# led_table_final.net
KiCad netlist of a schematic drawn in EAGLE
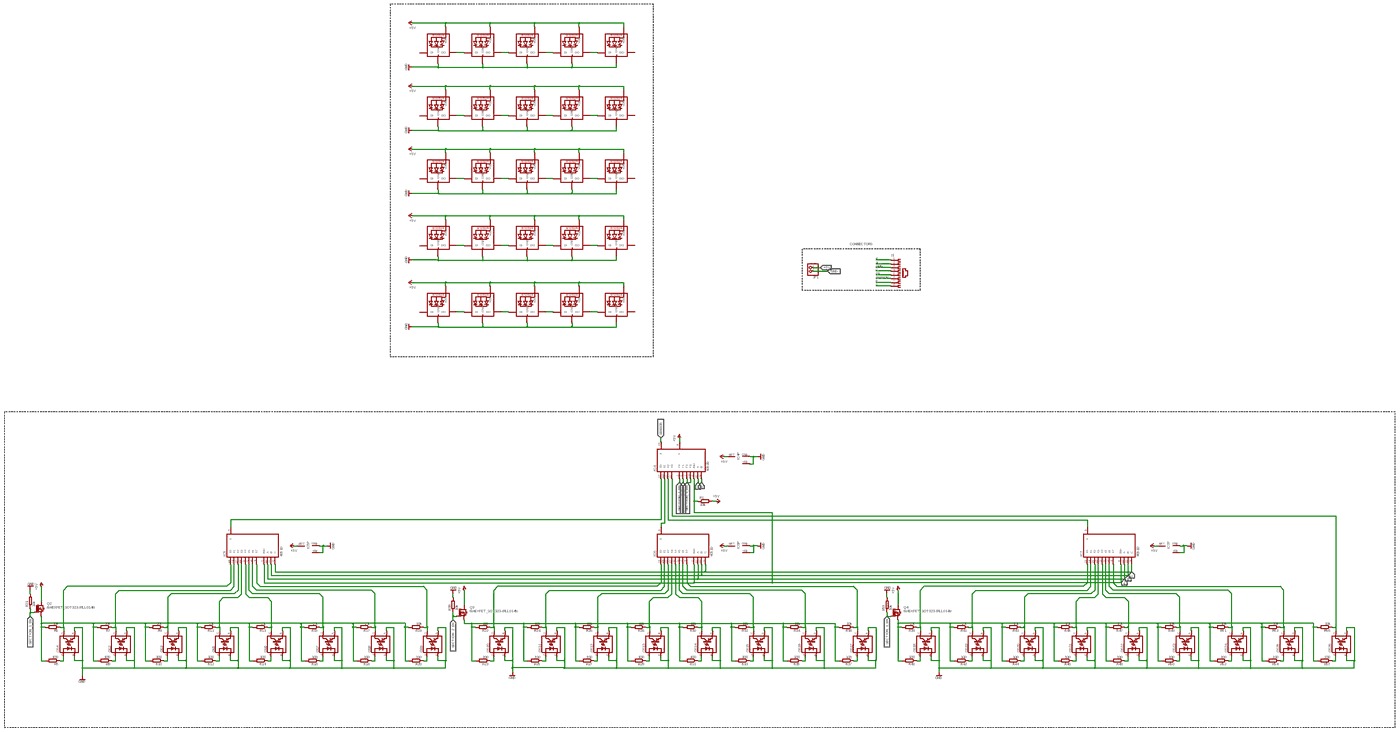
[diagram p0: schematic, sheet 1, overview]
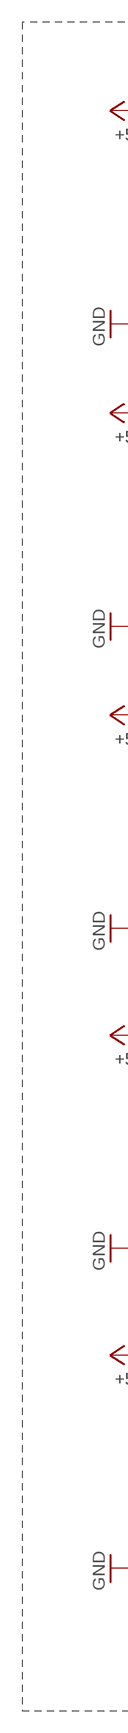
[diagram p1: schematic, sheet 1, part 1 of 5]
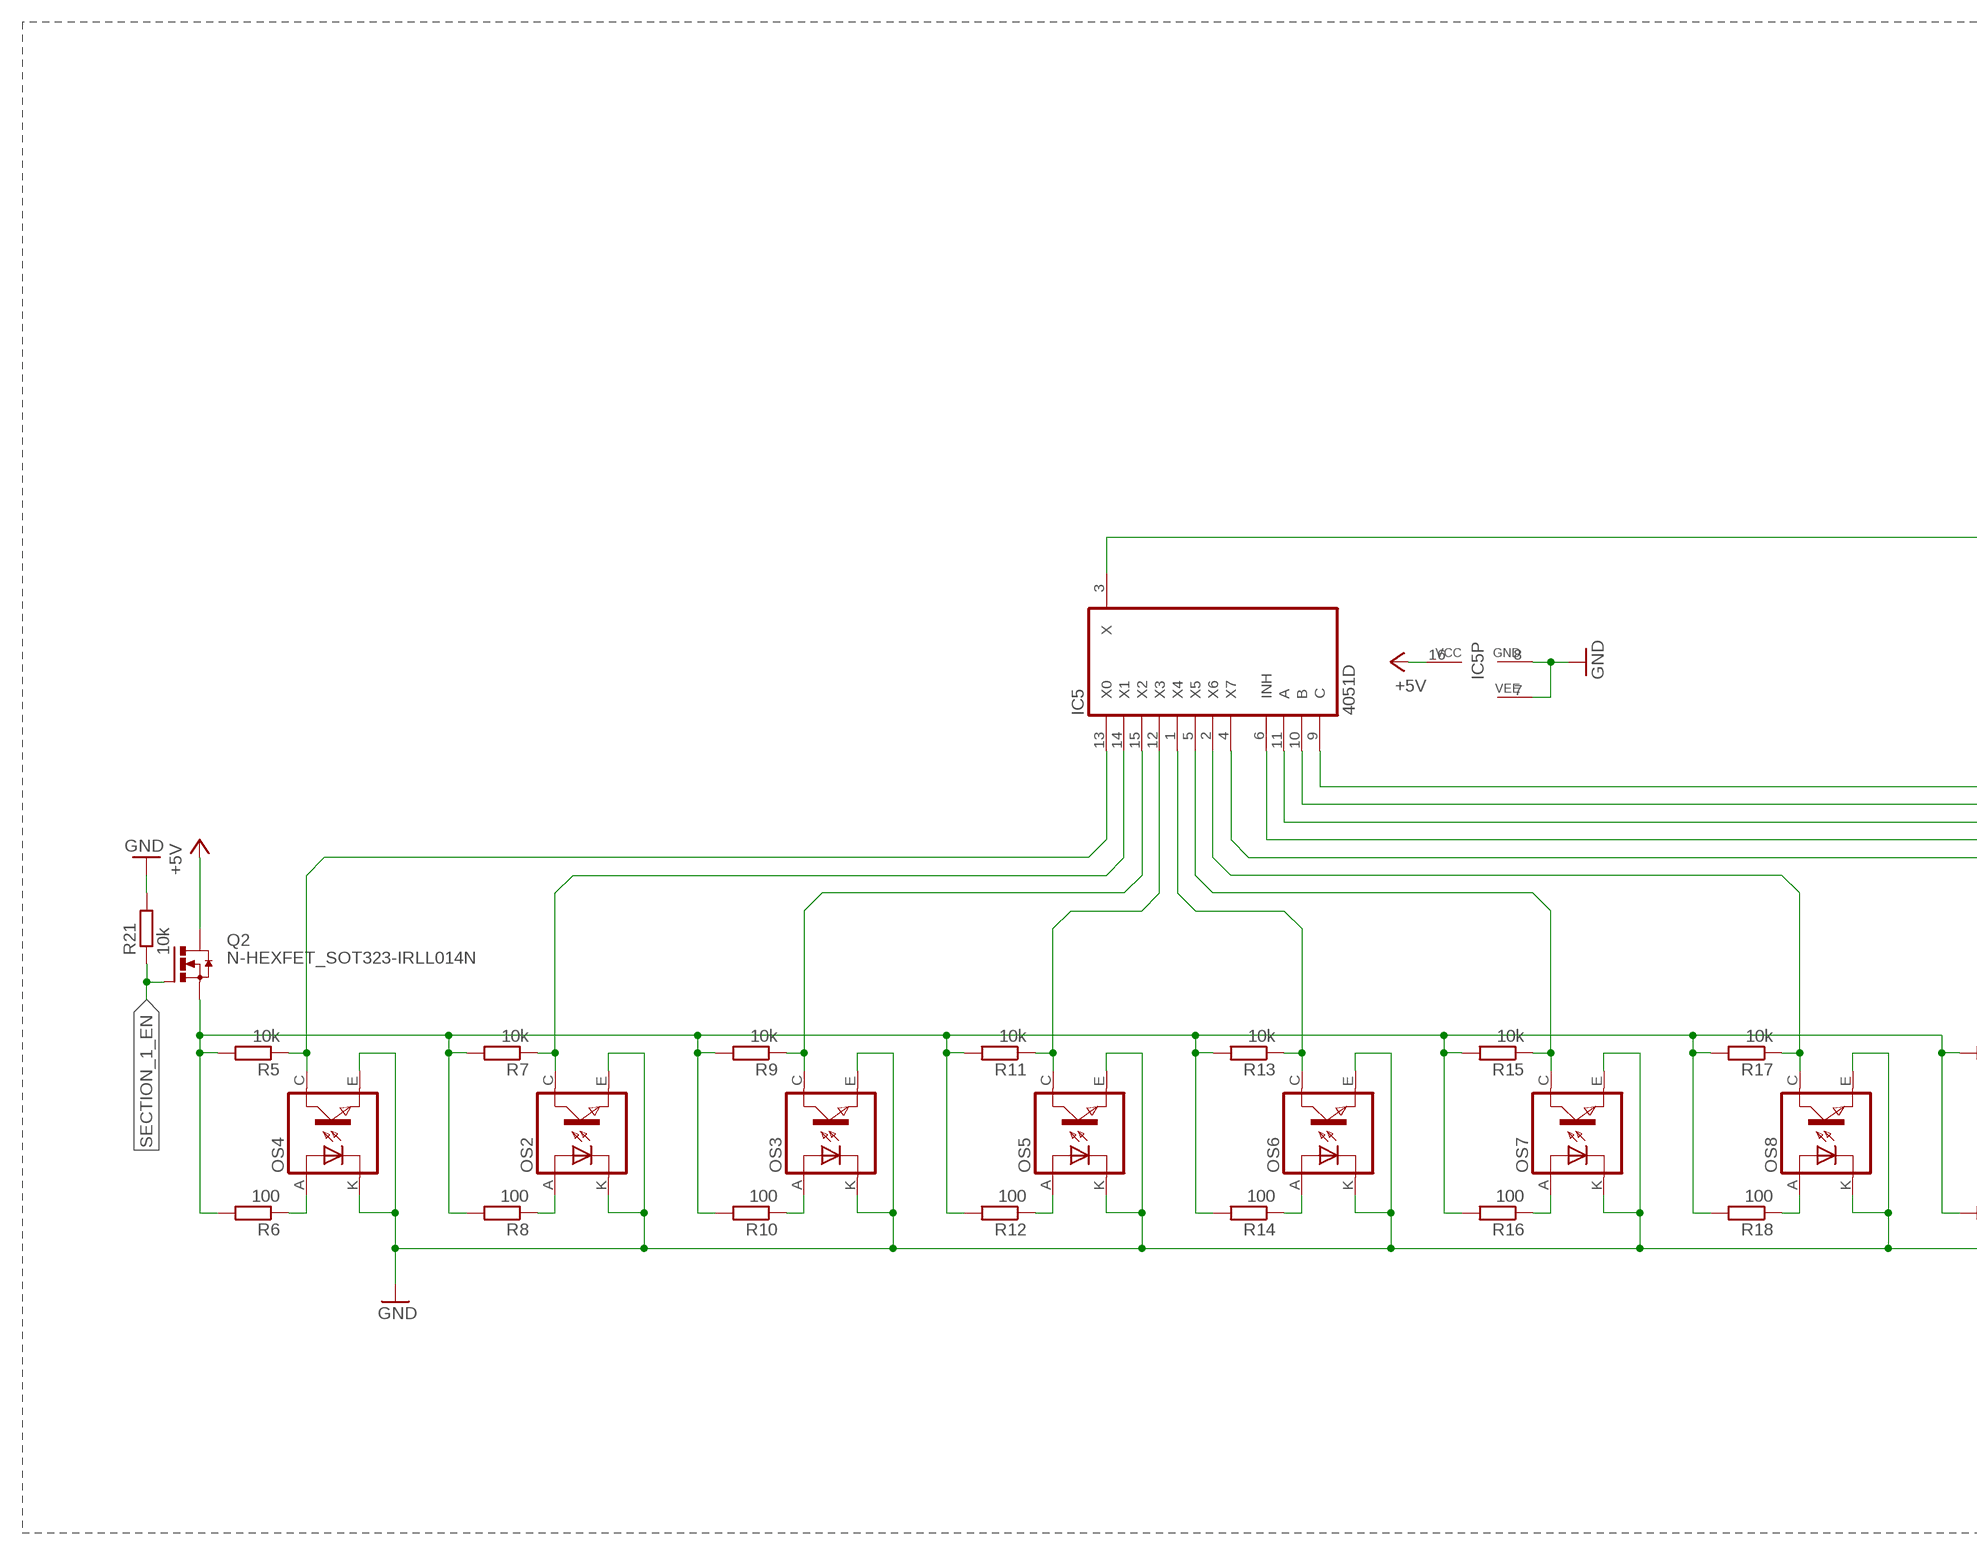
[diagram p2: schematic, sheet 1, part 2 of 5]
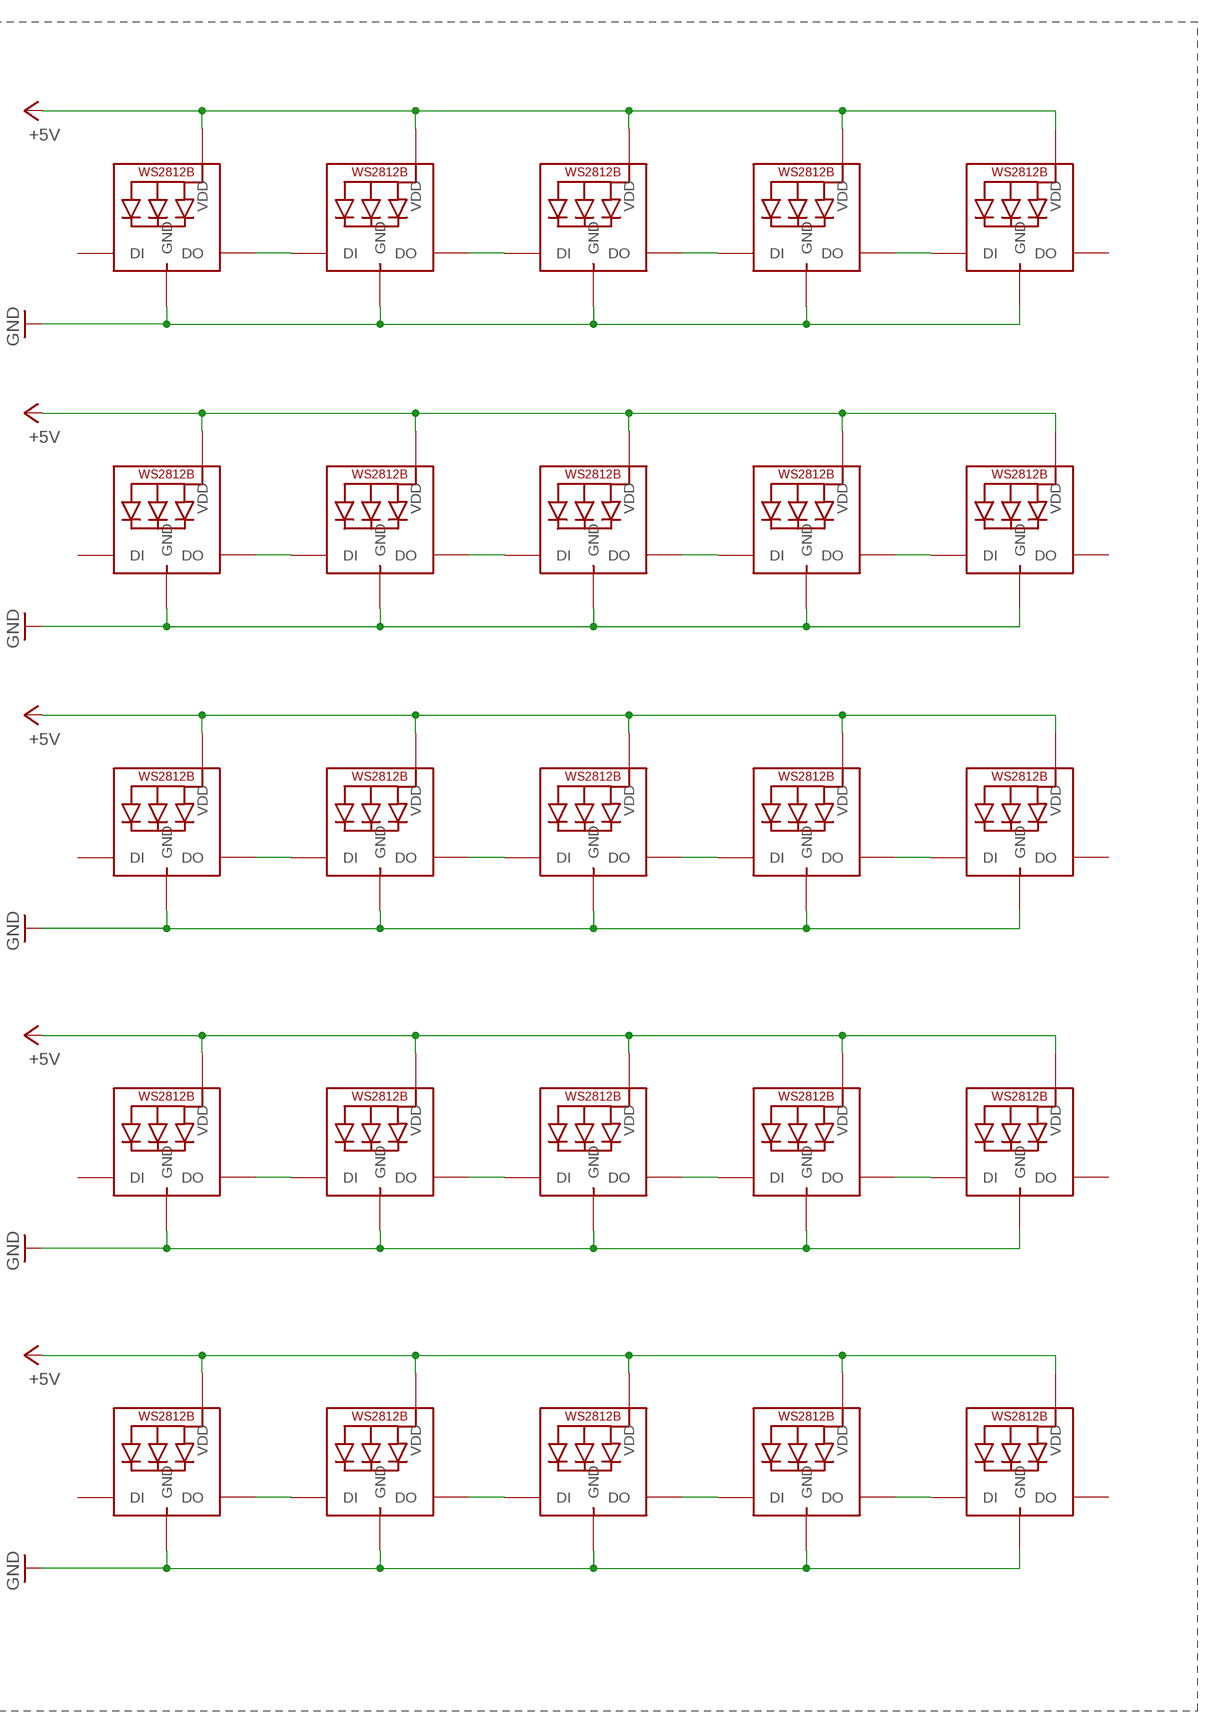
[diagram p3: schematic, sheet 1, part 3 of 5]
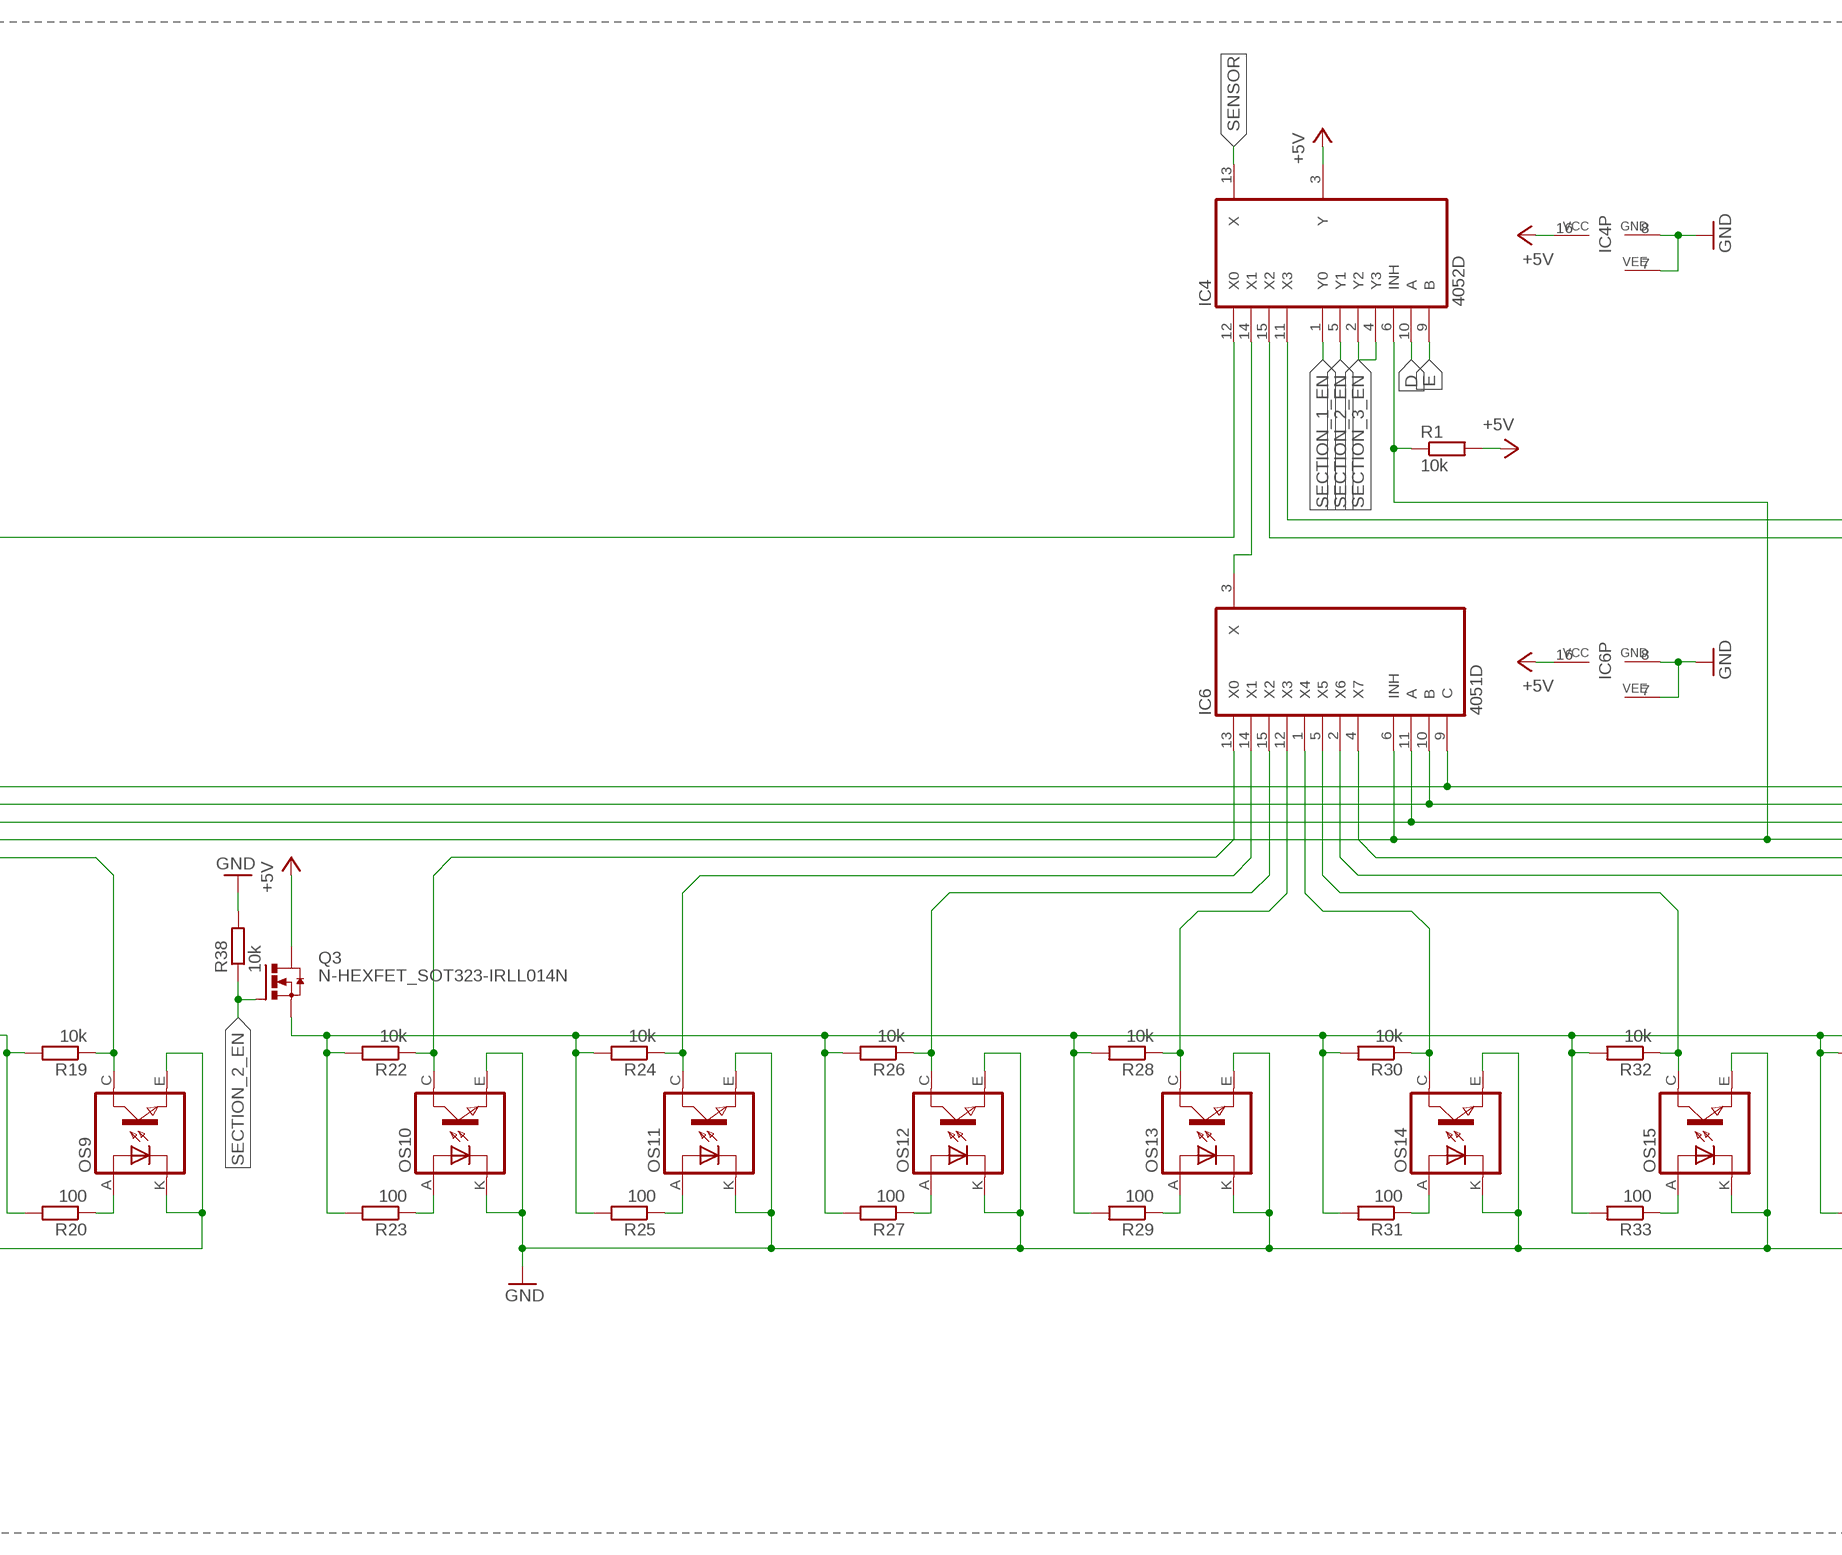
[diagram p4: schematic, sheet 1, part 4 of 5]
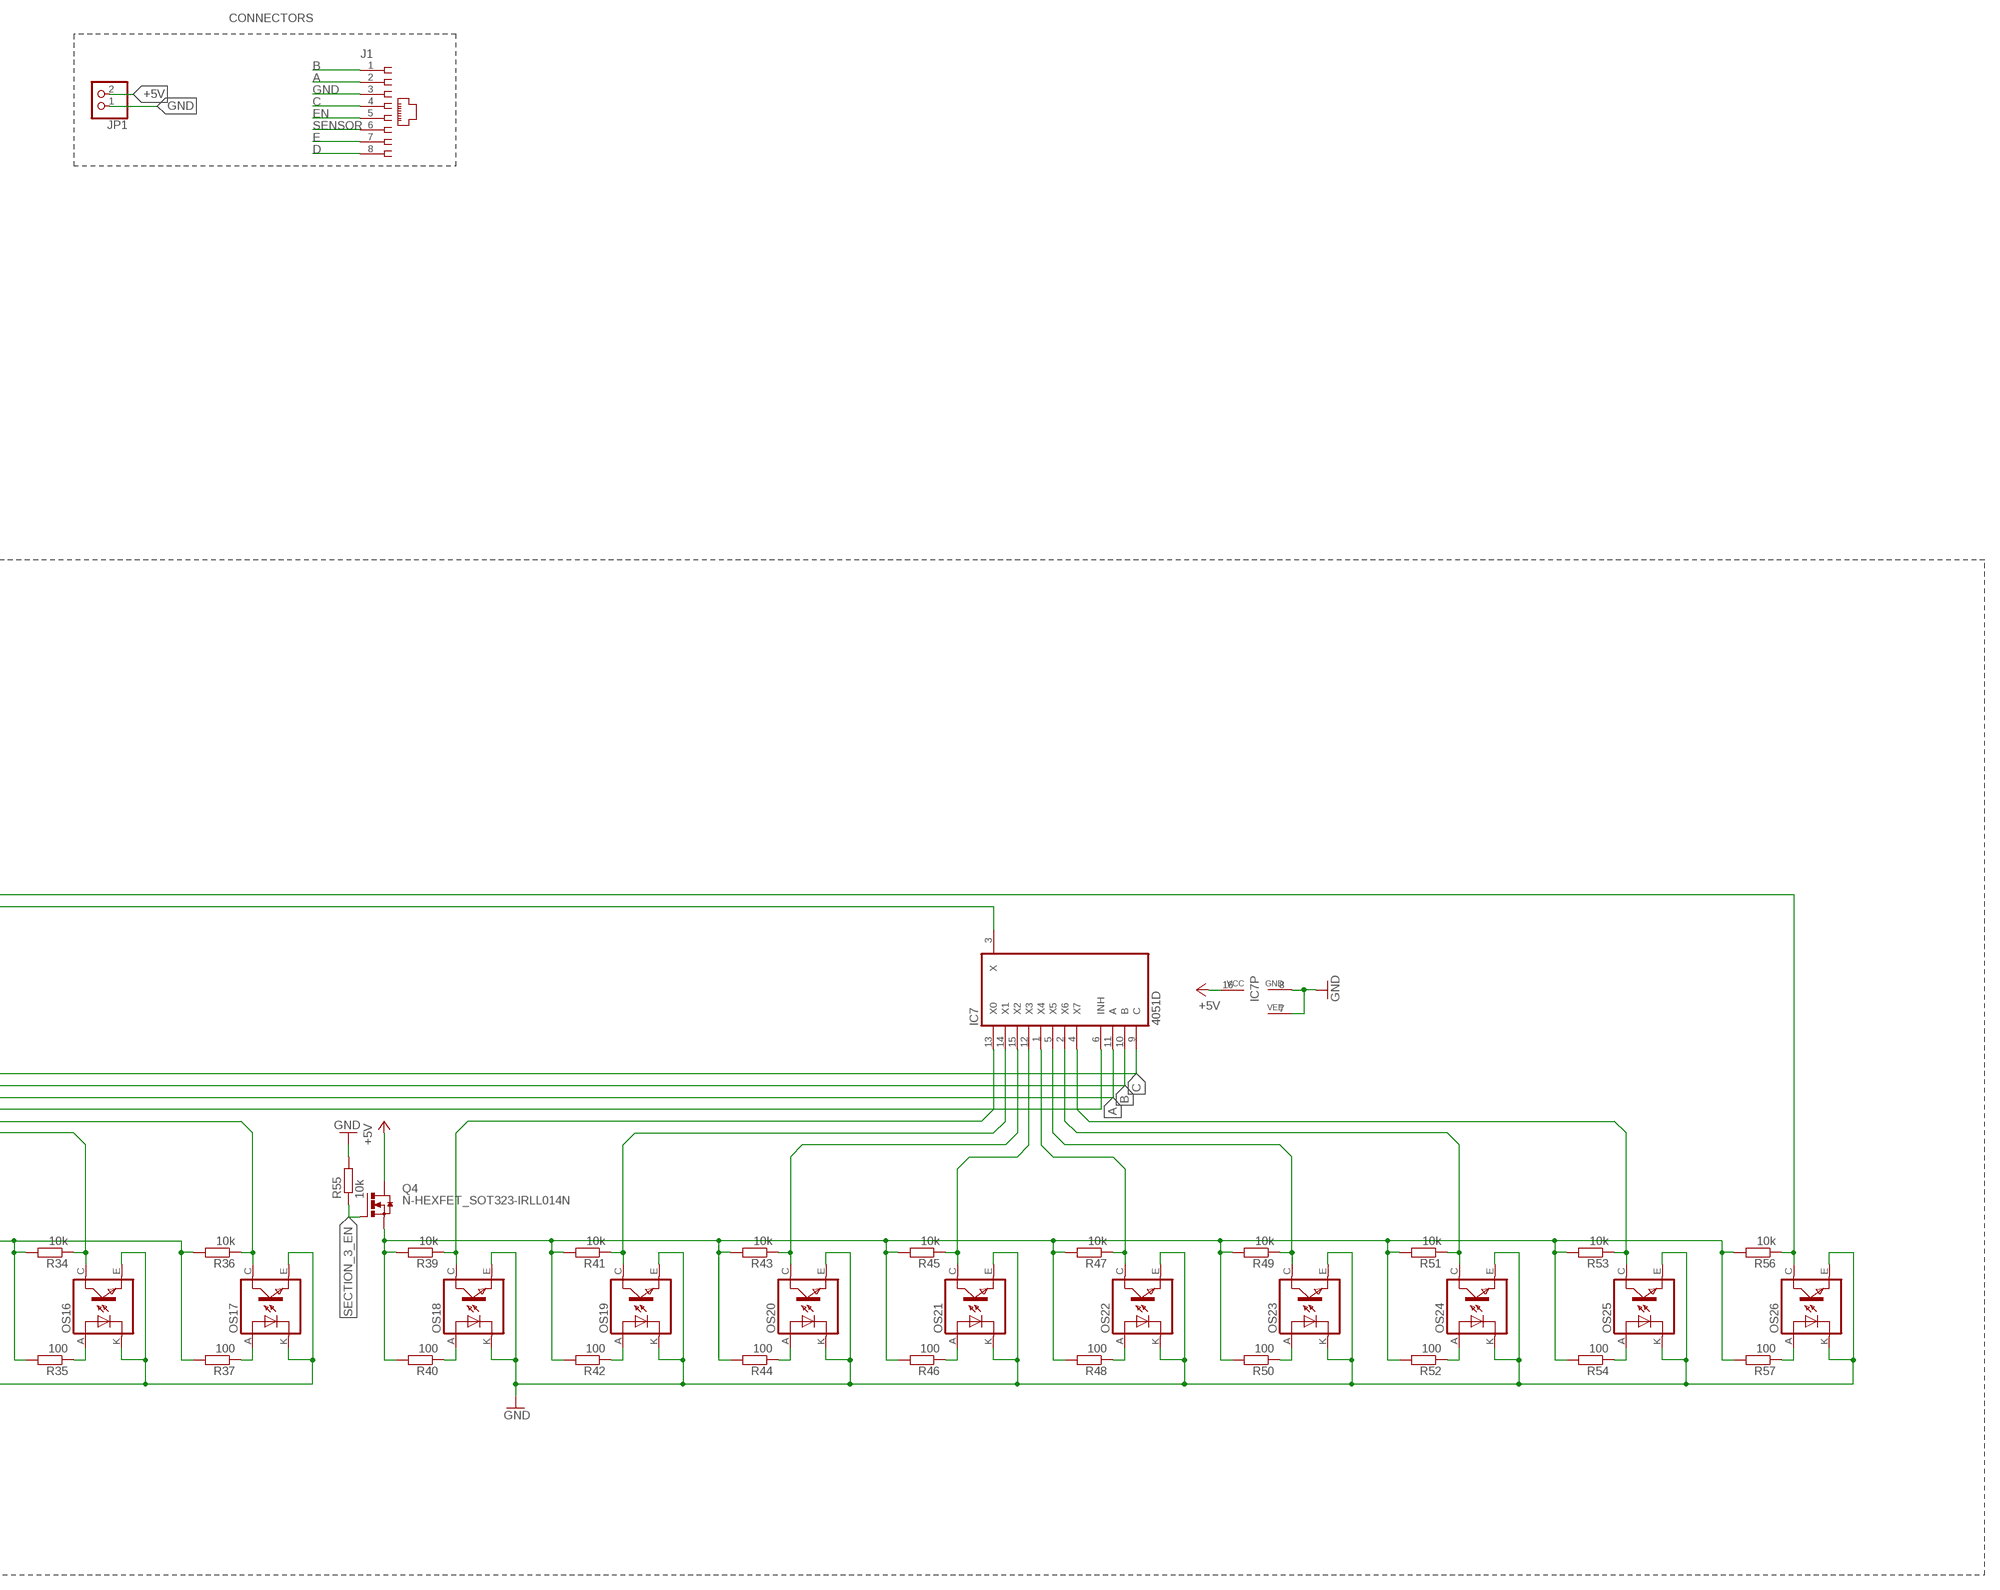
[diagram p5: schematic, sheet 1, part 5 of 5]

(export (version "E")
  (design (tool "Eeschema 10.0.6"))
  (components
    (comp (ref "IC4")
      (value "4052D")
      (footprint "eagle-import:SO16")
      (libsource (lib "eagle-import") (part "4052D"))
    )
    (comp (ref "IC5")
      (value "4051D")
      (footprint "eagle-import:SO16")
      (libsource (lib "eagle-import") (part "4051D"))
    )
    (comp (ref "IC6")
      (value "4051D")
      (footprint "eagle-import:SO16")
      (libsource (lib "eagle-import") (part "4051D"))
    )
    (comp (ref "IC7")
      (value "4051D")
      (footprint "eagle-import:SO16")
      (libsource (lib "eagle-import") (part "4051D"))
    )
    (comp (ref "J1")
      (value "556416-1")
      (footprint "eagle-import:556416-1")
      (libsource (lib "eagle-import") (part "556416-1"))
    )
    (comp (ref "JP1")
      (value "PINHD-1X2")
      (footprint "eagle-import:1X02")
      (libsource (lib "eagle-import") (part "PINHD-1X2"))
    )
    (comp (ref "LED1")
      (value "WS2812B")
      (footprint "eagle-import:WS2812B_ON_STRIP")
      (libsource (lib "eagle-import") (part "WS2812B"))
    )
    (comp (ref "LED2")
      (value "WS2812B")
      (footprint "eagle-import:WS2812B_ON_STRIP")
      (libsource (lib "eagle-import") (part "WS2812B"))
    )
    (comp (ref "LED3")
      (value "WS2812B")
      (footprint "eagle-import:WS2812B_ON_STRIP")
      (libsource (lib "eagle-import") (part "WS2812B"))
    )
    (comp (ref "LED4")
      (value "WS2812B")
      (footprint "eagle-import:WS2812B_ON_STRIP")
      (libsource (lib "eagle-import") (part "WS2812B"))
    )
    (comp (ref "LED5")
      (value "WS2812B")
      (footprint "eagle-import:WS2812B_ON_STRIP")
      (libsource (lib "eagle-import") (part "WS2812B"))
    )
    (comp (ref "LED6")
      (value "WS2812B")
      (footprint "eagle-import:WS2812B_ON_STRIP")
      (libsource (lib "eagle-import") (part "WS2812B"))
    )
    (comp (ref "LED7")
      (value "WS2812B")
      (footprint "eagle-import:WS2812B_ON_STRIP")
      (libsource (lib "eagle-import") (part "WS2812B"))
    )
    (comp (ref "LED8")
      (value "WS2812B")
      (footprint "eagle-import:WS2812B_ON_STRIP")
      (libsource (lib "eagle-import") (part "WS2812B"))
    )
    (comp (ref "LED9")
      (value "WS2812B")
      (footprint "eagle-import:WS2812B_ON_STRIP")
      (libsource (lib "eagle-import") (part "WS2812B"))
    )
    (comp (ref "LED10")
      (value "WS2812B")
      (footprint "eagle-import:WS2812B_ON_STRIP")
      (libsource (lib "eagle-import") (part "WS2812B"))
    )
    (comp (ref "LED11")
      (value "WS2812B")
      (footprint "eagle-import:WS2812B_ON_STRIP")
      (libsource (lib "eagle-import") (part "WS2812B"))
    )
    (comp (ref "LED12")
      (value "WS2812B")
      (footprint "eagle-import:WS2812B_ON_STRIP")
      (libsource (lib "eagle-import") (part "WS2812B"))
    )
    (comp (ref "LED13")
      (value "WS2812B")
      (footprint "eagle-import:WS2812B_ON_STRIP")
      (libsource (lib "eagle-import") (part "WS2812B"))
    )
    (comp (ref "LED14")
      (value "WS2812B")
      (footprint "eagle-import:WS2812B_ON_STRIP")
      (libsource (lib "eagle-import") (part "WS2812B"))
    )
    (comp (ref "LED15")
      (value "WS2812B")
      (footprint "eagle-import:WS2812B_ON_STRIP")
      (libsource (lib "eagle-import") (part "WS2812B"))
    )
    (comp (ref "LED16")
      (value "WS2812B")
      (footprint "eagle-import:WS2812B_ON_STRIP")
      (libsource (lib "eagle-import") (part "WS2812B"))
    )
    (comp (ref "LED17")
      (value "WS2812B")
      (footprint "eagle-import:WS2812B_ON_STRIP")
      (libsource (lib "eagle-import") (part "WS2812B"))
    )
    (comp (ref "LED18")
      (value "WS2812B")
      (footprint "eagle-import:WS2812B_ON_STRIP")
      (libsource (lib "eagle-import") (part "WS2812B"))
    )
    (comp (ref "LED19")
      (value "WS2812B")
      (footprint "eagle-import:WS2812B_ON_STRIP")
      (libsource (lib "eagle-import") (part "WS2812B"))
    )
    (comp (ref "LED20")
      (value "WS2812B")
      (footprint "eagle-import:WS2812B_ON_STRIP")
      (libsource (lib "eagle-import") (part "WS2812B"))
    )
    (comp (ref "LED21")
      (value "WS2812B")
      (footprint "eagle-import:WS2812B_ON_STRIP")
      (libsource (lib "eagle-import") (part "WS2812B"))
    )
    (comp (ref "LED22")
      (value "WS2812B")
      (footprint "eagle-import:WS2812B_ON_STRIP")
      (libsource (lib "eagle-import") (part "WS2812B"))
    )
    (comp (ref "LED23")
      (value "WS2812B")
      (footprint "eagle-import:WS2812B_ON_STRIP")
      (libsource (lib "eagle-import") (part "WS2812B"))
    )
    (comp (ref "LED24")
      (value "WS2812B")
      (footprint "eagle-import:WS2812B_ON_STRIP")
      (libsource (lib "eagle-import") (part "WS2812B"))
    )
    (comp (ref "LED25")
      (value "WS2812B")
      (footprint "eagle-import:WS2812B_ON_STRIP")
      (libsource (lib "eagle-import") (part "WS2812B"))
    )
    (comp (ref "OS2")
      (value "TCRT5000")
      (footprint "eagle-import:TCRT5000")
      (libsource (lib "eagle-import") (part "TCRT5000"))
    )
    (comp (ref "OS3")
      (value "TCRT5000")
      (footprint "eagle-import:TCRT5000")
      (libsource (lib "eagle-import") (part "TCRT5000"))
    )
    (comp (ref "OS4")
      (value "TCRT5000")
      (footprint "eagle-import:TCRT5000")
      (libsource (lib "eagle-import") (part "TCRT5000"))
    )
    (comp (ref "OS5")
      (value "TCRT5000")
      (footprint "eagle-import:TCRT5000")
      (libsource (lib "eagle-import") (part "TCRT5000"))
    )
    (comp (ref "OS6")
      (value "TCRT5000")
      (footprint "eagle-import:TCRT5000")
      (libsource (lib "eagle-import") (part "TCRT5000"))
    )
    (comp (ref "OS7")
      (value "TCRT5000")
      (footprint "eagle-import:TCRT5000")
      (libsource (lib "eagle-import") (part "TCRT5000"))
    )
    (comp (ref "OS8")
      (value "TCRT5000")
      (footprint "eagle-import:TCRT5000")
      (libsource (lib "eagle-import") (part "TCRT5000"))
    )
    (comp (ref "OS9")
      (value "TCRT5000")
      (footprint "eagle-import:TCRT5000")
      (libsource (lib "eagle-import") (part "TCRT5000"))
    )
    (comp (ref "OS10")
      (value "TCRT5000")
      (footprint "eagle-import:TCRT5000")
      (libsource (lib "eagle-import") (part "TCRT5000"))
    )
    (comp (ref "OS11")
      (value "TCRT5000")
      (footprint "eagle-import:TCRT5000")
      (libsource (lib "eagle-import") (part "TCRT5000"))
    )
    (comp (ref "OS12")
      (value "TCRT5000")
      (footprint "eagle-import:TCRT5000")
      (libsource (lib "eagle-import") (part "TCRT5000"))
    )
    (comp (ref "OS13")
      (value "TCRT5000")
      (footprint "eagle-import:TCRT5000")
      (libsource (lib "eagle-import") (part "TCRT5000"))
    )
    (comp (ref "OS14")
      (value "TCRT5000")
      (footprint "eagle-import:TCRT5000")
      (libsource (lib "eagle-import") (part "TCRT5000"))
    )
    (comp (ref "OS15")
      (value "TCRT5000")
      (footprint "eagle-import:TCRT5000")
      (libsource (lib "eagle-import") (part "TCRT5000"))
    )
    (comp (ref "OS16")
      (value "TCRT5000")
      (footprint "eagle-import:TCRT5000")
      (libsource (lib "eagle-import") (part "TCRT5000"))
    )
    (comp (ref "OS17")
      (value "TCRT5000")
      (footprint "eagle-import:TCRT5000")
      (libsource (lib "eagle-import") (part "TCRT5000"))
    )
    (comp (ref "OS18")
      (value "TCRT5000")
      (footprint "eagle-import:TCRT5000")
      (libsource (lib "eagle-import") (part "TCRT5000"))
    )
    (comp (ref "OS19")
      (value "TCRT5000")
      (footprint "eagle-import:TCRT5000")
      (libsource (lib "eagle-import") (part "TCRT5000"))
    )
    (comp (ref "OS20")
      (value "TCRT5000")
      (footprint "eagle-import:TCRT5000")
      (libsource (lib "eagle-import") (part "TCRT5000"))
    )
    (comp (ref "OS21")
      (value "TCRT5000")
      (footprint "eagle-import:TCRT5000")
      (libsource (lib "eagle-import") (part "TCRT5000"))
    )
    (comp (ref "OS22")
      (value "TCRT5000")
      (footprint "eagle-import:TCRT5000")
      (libsource (lib "eagle-import") (part "TCRT5000"))
    )
    (comp (ref "OS23")
      (value "TCRT5000")
      (footprint "eagle-import:TCRT5000")
      (libsource (lib "eagle-import") (part "TCRT5000"))
    )
    (comp (ref "OS24")
      (value "TCRT5000")
      (footprint "eagle-import:TCRT5000")
      (libsource (lib "eagle-import") (part "TCRT5000"))
    )
    (comp (ref "OS25")
      (value "TCRT5000")
      (footprint "eagle-import:TCRT5000")
      (libsource (lib "eagle-import") (part "TCRT5000"))
    )
    (comp (ref "OS26")
      (value "TCRT5000")
      (footprint "eagle-import:TCRT5000")
      (libsource (lib "eagle-import") (part "TCRT5000"))
    )
    (comp (ref "Q2")
      (value "N-HEXFET_SOT323-IRLL014N")
      (footprint "eagle-import:SOT223")
      (libsource (lib "eagle-import") (part "N-HEXFET_?-SOT323IRLL014N"))
    )
    (comp (ref "Q3")
      (value "N-HEXFET_SOT323-IRLL014N")
      (footprint "eagle-import:SOT223")
      (libsource (lib "eagle-import") (part "N-HEXFET_?-SOT323IRLL014N"))
    )
    (comp (ref "Q4")
      (value "N-HEXFET_SOT323-IRLL014N")
      (footprint "eagle-import:SOT223")
      (libsource (lib "eagle-import") (part "N-HEXFET_?-SOT323IRLL014N"))
    )
    (comp (ref "R1")
      (value "10k")
      (footprint "eagle-import:R1206")
      (libsource (lib "eagle-import") (part "R-EU_R1206"))
    )
    (comp (ref "R5")
      (value "10k")
      (footprint "eagle-import:R1206")
      (libsource (lib "eagle-import") (part "R-EU_R1206"))
    )
    (comp (ref "R6")
      (value "100")
      (footprint "eagle-import:R1206")
      (libsource (lib "eagle-import") (part "R-EU_R1206"))
    )
    (comp (ref "R7")
      (value "10k")
      (footprint "eagle-import:R1206")
      (libsource (lib "eagle-import") (part "R-EU_R1206"))
    )
    (comp (ref "R8")
      (value "100")
      (footprint "eagle-import:R1206")
      (libsource (lib "eagle-import") (part "R-EU_R1206"))
    )
    (comp (ref "R9")
      (value "10k")
      (footprint "eagle-import:R1206")
      (libsource (lib "eagle-import") (part "R-EU_R1206"))
    )
    (comp (ref "R10")
      (value "100")
      (footprint "eagle-import:R1206")
      (libsource (lib "eagle-import") (part "R-EU_R1206"))
    )
    (comp (ref "R11")
      (value "10k")
      (footprint "eagle-import:R1206")
      (libsource (lib "eagle-import") (part "R-EU_R1206"))
    )
    (comp (ref "R12")
      (value "100")
      (footprint "eagle-import:R1206")
      (libsource (lib "eagle-import") (part "R-EU_R1206"))
    )
    (comp (ref "R13")
      (value "10k")
      (footprint "eagle-import:R1206")
      (libsource (lib "eagle-import") (part "R-EU_R1206"))
    )
    (comp (ref "R14")
      (value "100")
      (footprint "eagle-import:R1206")
      (libsource (lib "eagle-import") (part "R-EU_R1206"))
    )
    (comp (ref "R15")
      (value "10k")
      (footprint "eagle-import:R1206")
      (libsource (lib "eagle-import") (part "R-EU_R1206"))
    )
    (comp (ref "R16")
      (value "100")
      (footprint "eagle-import:R1206")
      (libsource (lib "eagle-import") (part "R-EU_R1206"))
    )
    (comp (ref "R17")
      (value "10k")
      (footprint "eagle-import:R1206")
      (libsource (lib "eagle-import") (part "R-EU_R1206"))
    )
    (comp (ref "R18")
      (value "100")
      (footprint "eagle-import:R1206")
      (libsource (lib "eagle-import") (part "R-EU_R1206"))
    )
    (comp (ref "R19")
      (value "10k")
      (footprint "eagle-import:R1206")
      (libsource (lib "eagle-import") (part "R-EU_R1206"))
    )
    (comp (ref "R20")
      (value "100")
      (footprint "eagle-import:R1206")
      (libsource (lib "eagle-import") (part "R-EU_R1206"))
    )
    (comp (ref "R21")
      (value "10k")
      (footprint "eagle-import:R1206")
      (libsource (lib "eagle-import") (part "R-EU_R1206"))
    )
    (comp (ref "R22")
      (value "10k")
      (footprint "eagle-import:R1206")
      (libsource (lib "eagle-import") (part "R-EU_R1206"))
    )
    (comp (ref "R23")
      (value "100")
      (footprint "eagle-import:R1206")
      (libsource (lib "eagle-import") (part "R-EU_R1206"))
    )
    (comp (ref "R24")
      (value "10k")
      (footprint "eagle-import:R1206")
      (libsource (lib "eagle-import") (part "R-EU_R1206"))
    )
    (comp (ref "R25")
      (value "100")
      (footprint "eagle-import:R1206")
      (libsource (lib "eagle-import") (part "R-EU_R1206"))
    )
    (comp (ref "R26")
      (value "10k")
      (footprint "eagle-import:R1206")
      (libsource (lib "eagle-import") (part "R-EU_R1206"))
    )
    (comp (ref "R27")
      (value "100")
      (footprint "eagle-import:R1206")
      (libsource (lib "eagle-import") (part "R-EU_R1206"))
    )
    (comp (ref "R28")
      (value "10k")
      (footprint "eagle-import:R1206")
      (libsource (lib "eagle-import") (part "R-EU_R1206"))
    )
    (comp (ref "R29")
      (value "100")
      (footprint "eagle-import:R1206")
      (libsource (lib "eagle-import") (part "R-EU_R1206"))
    )
    (comp (ref "R30")
      (value "10k")
      (footprint "eagle-import:R1206")
      (libsource (lib "eagle-import") (part "R-EU_R1206"))
    )
    (comp (ref "R31")
      (value "100")
      (footprint "eagle-import:R1206")
      (libsource (lib "eagle-import") (part "R-EU_R1206"))
    )
    (comp (ref "R32")
      (value "10k")
      (footprint "eagle-import:R1206")
      (libsource (lib "eagle-import") (part "R-EU_R1206"))
    )
    (comp (ref "R33")
      (value "100")
      (footprint "eagle-import:R1206")
      (libsource (lib "eagle-import") (part "R-EU_R1206"))
    )
    (comp (ref "R34")
      (value "10k")
      (footprint "eagle-import:R1206")
      (libsource (lib "eagle-import") (part "R-EU_R1206"))
    )
    (comp (ref "R35")
      (value "100")
      (footprint "eagle-import:R1206")
      (libsource (lib "eagle-import") (part "R-EU_R1206"))
    )
    (comp (ref "R36")
      (value "10k")
      (footprint "eagle-import:R1206")
      (libsource (lib "eagle-import") (part "R-EU_R1206"))
    )
    (comp (ref "R37")
      (value "100")
      (footprint "eagle-import:R1206")
      (libsource (lib "eagle-import") (part "R-EU_R1206"))
    )
    (comp (ref "R38")
      (value "10k")
      (footprint "eagle-import:R1206")
      (libsource (lib "eagle-import") (part "R-EU_R1206"))
    )
    (comp (ref "R39")
      (value "10k")
      (footprint "eagle-import:R1206")
      (libsource (lib "eagle-import") (part "R-EU_R1206"))
    )
    (comp (ref "R40")
      (value "100")
      (footprint "eagle-import:R1206")
      (libsource (lib "eagle-import") (part "R-EU_R1206"))
    )
    (comp (ref "R41")
      (value "10k")
      (footprint "eagle-import:R1206")
      (libsource (lib "eagle-import") (part "R-EU_R1206"))
    )
    (comp (ref "R42")
      (value "100")
      (footprint "eagle-import:R1206")
      (libsource (lib "eagle-import") (part "R-EU_R1206"))
    )
    (comp (ref "R43")
      (value "10k")
      (footprint "eagle-import:R1206")
      (libsource (lib "eagle-import") (part "R-EU_R1206"))
    )
    (comp (ref "R44")
      (value "100")
      (footprint "eagle-import:R1206")
      (libsource (lib "eagle-import") (part "R-EU_R1206"))
    )
    (comp (ref "R45")
      (value "10k")
      (footprint "eagle-import:R1206")
      (libsource (lib "eagle-import") (part "R-EU_R1206"))
    )
    (comp (ref "R46")
      (value "100")
      (footprint "eagle-import:R1206")
      (libsource (lib "eagle-import") (part "R-EU_R1206"))
    )
    (comp (ref "R47")
      (value "10k")
      (footprint "eagle-import:R1206")
      (libsource (lib "eagle-import") (part "R-EU_R1206"))
    )
    (comp (ref "R48")
      (value "100")
      (footprint "eagle-import:R1206")
      (libsource (lib "eagle-import") (part "R-EU_R1206"))
    )
    (comp (ref "R49")
      (value "10k")
      (footprint "eagle-import:R1206")
      (libsource (lib "eagle-import") (part "R-EU_R1206"))
    )
    (comp (ref "R50")
      (value "100")
      (footprint "eagle-import:R1206")
      (libsource (lib "eagle-import") (part "R-EU_R1206"))
    )
    (comp (ref "R51")
      (value "10k")
      (footprint "eagle-import:R1206")
      (libsource (lib "eagle-import") (part "R-EU_R1206"))
    )
    (comp (ref "R52")
      (value "100")
      (footprint "eagle-import:R1206")
      (libsource (lib "eagle-import") (part "R-EU_R1206"))
    )
    (comp (ref "R53")
      (value "10k")
      (footprint "eagle-import:R1206")
      (libsource (lib "eagle-import") (part "R-EU_R1206"))
    )
    (comp (ref "R54")
      (value "100")
      (footprint "eagle-import:R1206")
      (libsource (lib "eagle-import") (part "R-EU_R1206"))
    )
    (comp (ref "R55")
      (value "10k")
      (footprint "eagle-import:R1206")
      (libsource (lib "eagle-import") (part "R-EU_R1206"))
    )
    (comp (ref "R56")
      (value "10k")
      (footprint "eagle-import:R1206")
      (libsource (lib "eagle-import") (part "R-EU_R1206"))
    )
    (comp (ref "R57")
      (value "100")
      (footprint "eagle-import:R1206")
      (libsource (lib "eagle-import") (part "R-EU_R1206"))
    )
  )
  (nets
    (net (code "1") (name "+5V") (class "Default")
      (node (ref "IC4") (pin "16") (pinfunction "VCC_16") (pintype "power_in"))
      (node (ref "IC4") (pin "3") (pinfunction "Y_3") (pintype "bidirectional"))
      (node (ref "IC5") (pin "16") (pinfunction "VCC_16") (pintype "power_in"))
      (node (ref "IC6") (pin "16") (pinfunction "VCC_16") (pintype "power_in"))
      (node (ref "IC7") (pin "16") (pinfunction "VCC_16") (pintype "power_in"))
      (node (ref "JP1") (pin "2") (pinfunction "2_2") (pintype "passive"))
      (node (ref "LED1") (pin "VCC_IN") (pinfunction "VDD_VCC_IN") (pintype "power_in"))
      (node (ref "LED1") (pin "VCC_OUT") (pinfunction "VDD_VCC_OUT") (pintype "power_in"))
      (node (ref "LED10") (pin "VCC_IN") (pinfunction "VDD_VCC_IN") (pintype "power_in"))
      (node (ref "LED10") (pin "VCC_OUT") (pinfunction "VDD_VCC_OUT") (pintype "power_in"))
      (node (ref "LED11") (pin "VCC_IN") (pinfunction "VDD_VCC_IN") (pintype "power_in"))
      (node (ref "LED11") (pin "VCC_OUT") (pinfunction "VDD_VCC_OUT") (pintype "power_in"))
      (node (ref "LED12") (pin "VCC_IN") (pinfunction "VDD_VCC_IN") (pintype "power_in"))
      (node (ref "LED12") (pin "VCC_OUT") (pinfunction "VDD_VCC_OUT") (pintype "power_in"))
      (node (ref "LED13") (pin "VCC_IN") (pinfunction "VDD_VCC_IN") (pintype "power_in"))
      (node (ref "LED13") (pin "VCC_OUT") (pinfunction "VDD_VCC_OUT") (pintype "power_in"))
      (node (ref "LED14") (pin "VCC_IN") (pinfunction "VDD_VCC_IN") (pintype "power_in"))
      (node (ref "LED14") (pin "VCC_OUT") (pinfunction "VDD_VCC_OUT") (pintype "power_in"))
      (node (ref "LED15") (pin "VCC_IN") (pinfunction "VDD_VCC_IN") (pintype "power_in"))
      (node (ref "LED15") (pin "VCC_OUT") (pinfunction "VDD_VCC_OUT") (pintype "power_in"))
      (node (ref "LED16") (pin "VCC_IN") (pinfunction "VDD_VCC_IN") (pintype "power_in"))
      (node (ref "LED16") (pin "VCC_OUT") (pinfunction "VDD_VCC_OUT") (pintype "power_in"))
      (node (ref "LED17") (pin "VCC_IN") (pinfunction "VDD_VCC_IN") (pintype "power_in"))
      (node (ref "LED17") (pin "VCC_OUT") (pinfunction "VDD_VCC_OUT") (pintype "power_in"))
      (node (ref "LED18") (pin "VCC_IN") (pinfunction "VDD_VCC_IN") (pintype "power_in"))
      (node (ref "LED18") (pin "VCC_OUT") (pinfunction "VDD_VCC_OUT") (pintype "power_in"))
      (node (ref "LED19") (pin "VCC_IN") (pinfunction "VDD_VCC_IN") (pintype "power_in"))
      (node (ref "LED19") (pin "VCC_OUT") (pinfunction "VDD_VCC_OUT") (pintype "power_in"))
      (node (ref "LED2") (pin "VCC_IN") (pinfunction "VDD_VCC_IN") (pintype "power_in"))
      (node (ref "LED2") (pin "VCC_OUT") (pinfunction "VDD_VCC_OUT") (pintype "power_in"))
      (node (ref "LED20") (pin "VCC_IN") (pinfunction "VDD_VCC_IN") (pintype "power_in"))
      (node (ref "LED20") (pin "VCC_OUT") (pinfunction "VDD_VCC_OUT") (pintype "power_in"))
      (node (ref "LED21") (pin "VCC_IN") (pinfunction "VDD_VCC_IN") (pintype "power_in"))
      (node (ref "LED21") (pin "VCC_OUT") (pinfunction "VDD_VCC_OUT") (pintype "power_in"))
      (node (ref "LED22") (pin "VCC_IN") (pinfunction "VDD_VCC_IN") (pintype "power_in"))
      (node (ref "LED22") (pin "VCC_OUT") (pinfunction "VDD_VCC_OUT") (pintype "power_in"))
      (node (ref "LED23") (pin "VCC_IN") (pinfunction "VDD_VCC_IN") (pintype "power_in"))
      (node (ref "LED23") (pin "VCC_OUT") (pinfunction "VDD_VCC_OUT") (pintype "power_in"))
      (node (ref "LED24") (pin "VCC_IN") (pinfunction "VDD_VCC_IN") (pintype "power_in"))
      (node (ref "LED24") (pin "VCC_OUT") (pinfunction "VDD_VCC_OUT") (pintype "power_in"))
      (node (ref "LED25") (pin "VCC_IN") (pinfunction "VDD_VCC_IN") (pintype "power_in"))
      (node (ref "LED25") (pin "VCC_OUT") (pinfunction "VDD_VCC_OUT") (pintype "power_in"))
      (node (ref "LED3") (pin "VCC_IN") (pinfunction "VDD_VCC_IN") (pintype "power_in"))
      (node (ref "LED3") (pin "VCC_OUT") (pinfunction "VDD_VCC_OUT") (pintype "power_in"))
      (node (ref "LED4") (pin "VCC_IN") (pinfunction "VDD_VCC_IN") (pintype "power_in"))
      (node (ref "LED4") (pin "VCC_OUT") (pinfunction "VDD_VCC_OUT") (pintype "power_in"))
      (node (ref "LED5") (pin "VCC_IN") (pinfunction "VDD_VCC_IN") (pintype "power_in"))
      (node (ref "LED5") (pin "VCC_OUT") (pinfunction "VDD_VCC_OUT") (pintype "power_in"))
      (node (ref "LED6") (pin "VCC_IN") (pinfunction "VDD_VCC_IN") (pintype "power_in"))
      (node (ref "LED6") (pin "VCC_OUT") (pinfunction "VDD_VCC_OUT") (pintype "power_in"))
      (node (ref "LED7") (pin "VCC_IN") (pinfunction "VDD_VCC_IN") (pintype "power_in"))
      (node (ref "LED7") (pin "VCC_OUT") (pinfunction "VDD_VCC_OUT") (pintype "power_in"))
      (node (ref "LED8") (pin "VCC_IN") (pinfunction "VDD_VCC_IN") (pintype "power_in"))
      (node (ref "LED8") (pin "VCC_OUT") (pinfunction "VDD_VCC_OUT") (pintype "power_in"))
      (node (ref "LED9") (pin "VCC_IN") (pinfunction "VDD_VCC_IN") (pintype "power_in"))
      (node (ref "LED9") (pin "VCC_OUT") (pinfunction "VDD_VCC_OUT") (pintype "power_in"))
      (node (ref "Q2") (pin "4") (pinfunction "D_4") (pintype "passive"))
      (node (ref "Q3") (pin "4") (pinfunction "D_4") (pintype "passive"))
      (node (ref "Q4") (pin "4") (pinfunction "D_4") (pintype "passive"))
      (node (ref "R1") (pin "2") (pinfunction "2_2") (pintype "passive"))
    )
    (net (code "2") (name "/EN") (class "Default")
      (node (ref "IC4") (pin "6") (pinfunction "INH_6") (pintype "input"))
      (node (ref "IC5") (pin "6") (pinfunction "INH_6") (pintype "input"))
      (node (ref "IC6") (pin "6") (pinfunction "INH_6") (pintype "input"))
      (node (ref "IC7") (pin "6") (pinfunction "INH_6") (pintype "input"))
      (node (ref "J1") (pin "5") (pinfunction "5_5") (pintype "passive"))
      (node (ref "R1") (pin "1") (pinfunction "1_1") (pintype "passive"))
    )
    (net (code "3") (name "A") (class "Default")
      (node (ref "IC5") (pin "11") (pinfunction "A_11") (pintype "input"))
      (node (ref "IC6") (pin "11") (pinfunction "A_11") (pintype "input"))
      (node (ref "IC7") (pin "11") (pinfunction "A_11") (pintype "input"))
      (node (ref "J1") (pin "2") (pinfunction "2_2") (pintype "passive"))
    )
    (net (code "4") (name "B") (class "Default")
      (node (ref "IC5") (pin "10") (pinfunction "B_10") (pintype "input"))
      (node (ref "IC6") (pin "10") (pinfunction "B_10") (pintype "input"))
      (node (ref "IC7") (pin "10") (pinfunction "B_10") (pintype "input"))
      (node (ref "J1") (pin "1") (pinfunction "1_1") (pintype "passive"))
    )
    (net (code "5") (name "C") (class "Default")
      (node (ref "IC5") (pin "9") (pinfunction "C_9") (pintype "input"))
      (node (ref "IC6") (pin "9") (pinfunction "C_9") (pintype "input"))
      (node (ref "IC7") (pin "9") (pinfunction "C_9") (pintype "input"))
      (node (ref "J1") (pin "4") (pinfunction "4_4") (pintype "passive"))
    )
    (net (code "6") (name "D") (class "Default")
      (node (ref "IC4") (pin "10") (pinfunction "A_10") (pintype "input"))
      (node (ref "J1") (pin "8") (pinfunction "8_8") (pintype "passive"))
    )
    (net (code "7") (name "E") (class "Default")
      (node (ref "IC4") (pin "9") (pinfunction "B_9") (pintype "input"))
      (node (ref "J1") (pin "7") (pinfunction "7_7") (pintype "passive"))
    )
    (net (code "8") (name "GND") (class "Default")
      (node (ref "IC4") (pin "7") (pinfunction "VEE_7") (pintype "power_in"))
      (node (ref "IC4") (pin "8") (pinfunction "GND_8") (pintype "power_in"))
      (node (ref "IC5") (pin "7") (pinfunction "VEE_7") (pintype "power_in"))
      (node (ref "IC5") (pin "8") (pinfunction "GND_8") (pintype "power_in"))
      (node (ref "IC6") (pin "7") (pinfunction "VEE_7") (pintype "power_in"))
      (node (ref "IC6") (pin "8") (pinfunction "GND_8") (pintype "power_in"))
      (node (ref "IC7") (pin "7") (pinfunction "VEE_7") (pintype "power_in"))
      (node (ref "IC7") (pin "8") (pinfunction "GND_8") (pintype "power_in"))
      (node (ref "J1") (pin "3") (pinfunction "3_3") (pintype "passive"))
      (node (ref "JP1") (pin "1") (pinfunction "1_1") (pintype "passive"))
      (node (ref "LED1") (pin "GND_IN") (pinfunction "GND_GND_IN") (pintype "power_in"))
      (node (ref "LED1") (pin "GND_OUT") (pinfunction "GND_GND_OUT") (pintype "power_in"))
      (node (ref "LED10") (pin "GND_IN") (pinfunction "GND_GND_IN") (pintype "power_in"))
      (node (ref "LED10") (pin "GND_OUT") (pinfunction "GND_GND_OUT") (pintype "power_in"))
      (node (ref "LED11") (pin "GND_IN") (pinfunction "GND_GND_IN") (pintype "power_in"))
      (node (ref "LED11") (pin "GND_OUT") (pinfunction "GND_GND_OUT") (pintype "power_in"))
      (node (ref "LED12") (pin "GND_IN") (pinfunction "GND_GND_IN") (pintype "power_in"))
      (node (ref "LED12") (pin "GND_OUT") (pinfunction "GND_GND_OUT") (pintype "power_in"))
      (node (ref "LED13") (pin "GND_IN") (pinfunction "GND_GND_IN") (pintype "power_in"))
      (node (ref "LED13") (pin "GND_OUT") (pinfunction "GND_GND_OUT") (pintype "power_in"))
      (node (ref "LED14") (pin "GND_IN") (pinfunction "GND_GND_IN") (pintype "power_in"))
      (node (ref "LED14") (pin "GND_OUT") (pinfunction "GND_GND_OUT") (pintype "power_in"))
      (node (ref "LED15") (pin "GND_IN") (pinfunction "GND_GND_IN") (pintype "power_in"))
      (node (ref "LED15") (pin "GND_OUT") (pinfunction "GND_GND_OUT") (pintype "power_in"))
      (node (ref "LED16") (pin "GND_IN") (pinfunction "GND_GND_IN") (pintype "power_in"))
      (node (ref "LED16") (pin "GND_OUT") (pinfunction "GND_GND_OUT") (pintype "power_in"))
      (node (ref "LED17") (pin "GND_IN") (pinfunction "GND_GND_IN") (pintype "power_in"))
      (node (ref "LED17") (pin "GND_OUT") (pinfunction "GND_GND_OUT") (pintype "power_in"))
      (node (ref "LED18") (pin "GND_IN") (pinfunction "GND_GND_IN") (pintype "power_in"))
      (node (ref "LED18") (pin "GND_OUT") (pinfunction "GND_GND_OUT") (pintype "power_in"))
      (node (ref "LED19") (pin "GND_IN") (pinfunction "GND_GND_IN") (pintype "power_in"))
      (node (ref "LED19") (pin "GND_OUT") (pinfunction "GND_GND_OUT") (pintype "power_in"))
      (node (ref "LED2") (pin "GND_IN") (pinfunction "GND_GND_IN") (pintype "power_in"))
      (node (ref "LED2") (pin "GND_OUT") (pinfunction "GND_GND_OUT") (pintype "power_in"))
      (node (ref "LED20") (pin "GND_IN") (pinfunction "GND_GND_IN") (pintype "power_in"))
      (node (ref "LED20") (pin "GND_OUT") (pinfunction "GND_GND_OUT") (pintype "power_in"))
      (node (ref "LED21") (pin "GND_IN") (pinfunction "GND_GND_IN") (pintype "power_in"))
      (node (ref "LED21") (pin "GND_OUT") (pinfunction "GND_GND_OUT") (pintype "power_in"))
      (node (ref "LED22") (pin "GND_IN") (pinfunction "GND_GND_IN") (pintype "power_in"))
      (node (ref "LED22") (pin "GND_OUT") (pinfunction "GND_GND_OUT") (pintype "power_in"))
      (node (ref "LED23") (pin "GND_IN") (pinfunction "GND_GND_IN") (pintype "power_in"))
      (node (ref "LED23") (pin "GND_OUT") (pinfunction "GND_GND_OUT") (pintype "power_in"))
      (node (ref "LED24") (pin "GND_IN") (pinfunction "GND_GND_IN") (pintype "power_in"))
      (node (ref "LED24") (pin "GND_OUT") (pinfunction "GND_GND_OUT") (pintype "power_in"))
      (node (ref "LED25") (pin "GND_IN") (pinfunction "GND_GND_IN") (pintype "power_in"))
      (node (ref "LED25") (pin "GND_OUT") (pinfunction "GND_GND_OUT") (pintype "power_in"))
      (node (ref "LED3") (pin "GND_IN") (pinfunction "GND_GND_IN") (pintype "power_in"))
      (node (ref "LED3") (pin "GND_OUT") (pinfunction "GND_GND_OUT") (pintype "power_in"))
      (node (ref "LED4") (pin "GND_IN") (pinfunction "GND_GND_IN") (pintype "power_in"))
      (node (ref "LED4") (pin "GND_OUT") (pinfunction "GND_GND_OUT") (pintype "power_in"))
      (node (ref "LED5") (pin "GND_IN") (pinfunction "GND_GND_IN") (pintype "power_in"))
      (node (ref "LED5") (pin "GND_OUT") (pinfunction "GND_GND_OUT") (pintype "power_in"))
      (node (ref "LED6") (pin "GND_IN") (pinfunction "GND_GND_IN") (pintype "power_in"))
      (node (ref "LED6") (pin "GND_OUT") (pinfunction "GND_GND_OUT") (pintype "power_in"))
      (node (ref "LED7") (pin "GND_IN") (pinfunction "GND_GND_IN") (pintype "power_in"))
      (node (ref "LED7") (pin "GND_OUT") (pinfunction "GND_GND_OUT") (pintype "power_in"))
      (node (ref "LED8") (pin "GND_IN") (pinfunction "GND_GND_IN") (pintype "power_in"))
      (node (ref "LED8") (pin "GND_OUT") (pinfunction "GND_GND_OUT") (pintype "power_in"))
      (node (ref "LED9") (pin "GND_IN") (pinfunction "GND_GND_IN") (pintype "power_in"))
      (node (ref "LED9") (pin "GND_OUT") (pinfunction "GND_GND_OUT") (pintype "power_in"))
      (node (ref "OS10") (pin "E") (pinfunction "EMITTER_E") (pintype "passive"))
      (node (ref "OS10") (pin "K") (pinfunction "CATHODE_K") (pintype "passive"))
      (node (ref "OS11") (pin "E") (pinfunction "EMITTER_E") (pintype "passive"))
      (node (ref "OS11") (pin "K") (pinfunction "CATHODE_K") (pintype "passive"))
      (node (ref "OS12") (pin "E") (pinfunction "EMITTER_E") (pintype "passive"))
      (node (ref "OS12") (pin "K") (pinfunction "CATHODE_K") (pintype "passive"))
      (node (ref "OS13") (pin "E") (pinfunction "EMITTER_E") (pintype "passive"))
      (node (ref "OS13") (pin "K") (pinfunction "CATHODE_K") (pintype "passive"))
      (node (ref "OS14") (pin "E") (pinfunction "EMITTER_E") (pintype "passive"))
      (node (ref "OS14") (pin "K") (pinfunction "CATHODE_K") (pintype "passive"))
      (node (ref "OS15") (pin "E") (pinfunction "EMITTER_E") (pintype "passive"))
      (node (ref "OS15") (pin "K") (pinfunction "CATHODE_K") (pintype "passive"))
      (node (ref "OS16") (pin "E") (pinfunction "EMITTER_E") (pintype "passive"))
      (node (ref "OS16") (pin "K") (pinfunction "CATHODE_K") (pintype "passive"))
      (node (ref "OS17") (pin "E") (pinfunction "EMITTER_E") (pintype "passive"))
      (node (ref "OS17") (pin "K") (pinfunction "CATHODE_K") (pintype "passive"))
      (node (ref "OS18") (pin "E") (pinfunction "EMITTER_E") (pintype "passive"))
      (node (ref "OS18") (pin "K") (pinfunction "CATHODE_K") (pintype "passive"))
      (node (ref "OS19") (pin "E") (pinfunction "EMITTER_E") (pintype "passive"))
      (node (ref "OS19") (pin "K") (pinfunction "CATHODE_K") (pintype "passive"))
      (node (ref "OS2") (pin "E") (pinfunction "EMITTER_E") (pintype "passive"))
      (node (ref "OS2") (pin "K") (pinfunction "CATHODE_K") (pintype "passive"))
      (node (ref "OS20") (pin "E") (pinfunction "EMITTER_E") (pintype "passive"))
      (node (ref "OS20") (pin "K") (pinfunction "CATHODE_K") (pintype "passive"))
      (node (ref "OS21") (pin "E") (pinfunction "EMITTER_E") (pintype "passive"))
      (node (ref "OS21") (pin "K") (pinfunction "CATHODE_K") (pintype "passive"))
      (node (ref "OS22") (pin "E") (pinfunction "EMITTER_E") (pintype "passive"))
      (node (ref "OS22") (pin "K") (pinfunction "CATHODE_K") (pintype "passive"))
      (node (ref "OS23") (pin "E") (pinfunction "EMITTER_E") (pintype "passive"))
      (node (ref "OS23") (pin "K") (pinfunction "CATHODE_K") (pintype "passive"))
      (node (ref "OS24") (pin "E") (pinfunction "EMITTER_E") (pintype "passive"))
      (node (ref "OS24") (pin "K") (pinfunction "CATHODE_K") (pintype "passive"))
      (node (ref "OS25") (pin "E") (pinfunction "EMITTER_E") (pintype "passive"))
      (node (ref "OS25") (pin "K") (pinfunction "CATHODE_K") (pintype "passive"))
      (node (ref "OS26") (pin "E") (pinfunction "EMITTER_E") (pintype "passive"))
      (node (ref "OS26") (pin "K") (pinfunction "CATHODE_K") (pintype "passive"))
      (node (ref "OS3") (pin "E") (pinfunction "EMITTER_E") (pintype "passive"))
      (node (ref "OS3") (pin "K") (pinfunction "CATHODE_K") (pintype "passive"))
      (node (ref "OS4") (pin "E") (pinfunction "EMITTER_E") (pintype "passive"))
      (node (ref "OS4") (pin "K") (pinfunction "CATHODE_K") (pintype "passive"))
      (node (ref "OS5") (pin "E") (pinfunction "EMITTER_E") (pintype "passive"))
      (node (ref "OS5") (pin "K") (pinfunction "CATHODE_K") (pintype "passive"))
      (node (ref "OS6") (pin "E") (pinfunction "EMITTER_E") (pintype "passive"))
      (node (ref "OS6") (pin "K") (pinfunction "CATHODE_K") (pintype "passive"))
      (node (ref "OS7") (pin "E") (pinfunction "EMITTER_E") (pintype "passive"))
      (node (ref "OS7") (pin "K") (pinfunction "CATHODE_K") (pintype "passive"))
      (node (ref "OS8") (pin "E") (pinfunction "EMITTER_E") (pintype "passive"))
      (node (ref "OS8") (pin "K") (pinfunction "CATHODE_K") (pintype "passive"))
      (node (ref "OS9") (pin "E") (pinfunction "EMITTER_E") (pintype "passive"))
      (node (ref "OS9") (pin "K") (pinfunction "CATHODE_K") (pintype "passive"))
      (node (ref "R21") (pin "2") (pinfunction "2_2") (pintype "passive"))
      (node (ref "R38") (pin "2") (pinfunction "2_2") (pintype "passive"))
      (node (ref "R55") (pin "2") (pinfunction "2_2") (pintype "passive"))
    )
    (net (code "9") (name "Net-(IC4A-X0)") (class "Default")
      (node (ref "IC4") (pin "12") (pinfunction "X0_12") (pintype "bidirectional"))
      (node (ref "IC5") (pin "3") (pinfunction "X_3") (pintype "bidirectional"))
    )
    (net (code "10") (name "Net-(IC4A-X1)") (class "Default")
      (node (ref "IC4") (pin "14") (pinfunction "X1_14") (pintype "bidirectional"))
      (node (ref "IC6") (pin "3") (pinfunction "X_3") (pintype "bidirectional"))
    )
    (net (code "11") (name "Net-(IC4A-X2)") (class "Default")
      (node (ref "IC4") (pin "15") (pinfunction "X2_15") (pintype "bidirectional"))
      (node (ref "IC7") (pin "3") (pinfunction "X_3") (pintype "bidirectional"))
    )
    (net (code "12") (name "Net-(IC4A-X3)") (class "Default")
      (node (ref "IC4") (pin "11") (pinfunction "X3_11") (pintype "bidirectional"))
      (node (ref "OS26") (pin "C") (pinfunction "COLLECTOR_C") (pintype "passive"))
      (node (ref "R56") (pin "1") (pinfunction "1_1") (pintype "passive"))
    )
    (net (code "13") (name "Net-(IC5A-X0)") (class "Default")
      (node (ref "IC5") (pin "13") (pinfunction "X0_13") (pintype "bidirectional"))
      (node (ref "OS4") (pin "C") (pinfunction "COLLECTOR_C") (pintype "passive"))
      (node (ref "R5") (pin "1") (pinfunction "1_1") (pintype "passive"))
    )
    (net (code "14") (name "Net-(IC5A-X1)") (class "Default")
      (node (ref "IC5") (pin "14") (pinfunction "X1_14") (pintype "bidirectional"))
      (node (ref "OS2") (pin "C") (pinfunction "COLLECTOR_C") (pintype "passive"))
      (node (ref "R7") (pin "1") (pinfunction "1_1") (pintype "passive"))
    )
    (net (code "15") (name "Net-(IC5A-X2)") (class "Default")
      (node (ref "IC5") (pin "15") (pinfunction "X2_15") (pintype "bidirectional"))
      (node (ref "OS3") (pin "C") (pinfunction "COLLECTOR_C") (pintype "passive"))
      (node (ref "R9") (pin "1") (pinfunction "1_1") (pintype "passive"))
    )
    (net (code "16") (name "Net-(IC5A-X3)") (class "Default")
      (node (ref "IC5") (pin "12") (pinfunction "X3_12") (pintype "bidirectional"))
      (node (ref "OS5") (pin "C") (pinfunction "COLLECTOR_C") (pintype "passive"))
      (node (ref "R11") (pin "1") (pinfunction "1_1") (pintype "passive"))
    )
    (net (code "17") (name "Net-(IC5A-X4)") (class "Default")
      (node (ref "IC5") (pin "1") (pinfunction "X4_1") (pintype "bidirectional"))
      (node (ref "OS6") (pin "C") (pinfunction "COLLECTOR_C") (pintype "passive"))
      (node (ref "R13") (pin "1") (pinfunction "1_1") (pintype "passive"))
    )
    (net (code "18") (name "Net-(IC5A-X5)") (class "Default")
      (node (ref "IC5") (pin "5") (pinfunction "X5_5") (pintype "bidirectional"))
      (node (ref "OS7") (pin "C") (pinfunction "COLLECTOR_C") (pintype "passive"))
      (node (ref "R15") (pin "1") (pinfunction "1_1") (pintype "passive"))
    )
    (net (code "19") (name "Net-(IC5A-X6)") (class "Default")
      (node (ref "IC5") (pin "2") (pinfunction "X6_2") (pintype "bidirectional"))
      (node (ref "OS8") (pin "C") (pinfunction "COLLECTOR_C") (pintype "passive"))
      (node (ref "R17") (pin "1") (pinfunction "1_1") (pintype "passive"))
    )
    (net (code "20") (name "Net-(IC5A-X7)") (class "Default")
      (node (ref "IC5") (pin "4") (pinfunction "X7_4") (pintype "bidirectional"))
      (node (ref "OS9") (pin "C") (pinfunction "COLLECTOR_C") (pintype "passive"))
      (node (ref "R19") (pin "1") (pinfunction "1_1") (pintype "passive"))
    )
    (net (code "21") (name "Net-(IC6A-X0)") (class "Default")
      (node (ref "IC6") (pin "13") (pinfunction "X0_13") (pintype "bidirectional"))
      (node (ref "OS10") (pin "C") (pinfunction "COLLECTOR_C") (pintype "passive"))
      (node (ref "R22") (pin "1") (pinfunction "1_1") (pintype "passive"))
    )
    (net (code "22") (name "Net-(IC6A-X1)") (class "Default")
      (node (ref "IC6") (pin "14") (pinfunction "X1_14") (pintype "bidirectional"))
      (node (ref "OS11") (pin "C") (pinfunction "COLLECTOR_C") (pintype "passive"))
      (node (ref "R24") (pin "1") (pinfunction "1_1") (pintype "passive"))
    )
    (net (code "23") (name "Net-(IC6A-X2)") (class "Default")
      (node (ref "IC6") (pin "15") (pinfunction "X2_15") (pintype "bidirectional"))
      (node (ref "OS12") (pin "C") (pinfunction "COLLECTOR_C") (pintype "passive"))
      (node (ref "R26") (pin "1") (pinfunction "1_1") (pintype "passive"))
    )
    (net (code "24") (name "Net-(IC6A-X3)") (class "Default")
      (node (ref "IC6") (pin "12") (pinfunction "X3_12") (pintype "bidirectional"))
      (node (ref "OS13") (pin "C") (pinfunction "COLLECTOR_C") (pintype "passive"))
      (node (ref "R28") (pin "1") (pinfunction "1_1") (pintype "passive"))
    )
    (net (code "25") (name "Net-(IC6A-X4)") (class "Default")
      (node (ref "IC6") (pin "1") (pinfunction "X4_1") (pintype "bidirectional"))
      (node (ref "OS14") (pin "C") (pinfunction "COLLECTOR_C") (pintype "passive"))
      (node (ref "R30") (pin "1") (pinfunction "1_1") (pintype "passive"))
    )
    (net (code "26") (name "Net-(IC6A-X5)") (class "Default")
      (node (ref "IC6") (pin "5") (pinfunction "X5_5") (pintype "bidirectional"))
      (node (ref "OS15") (pin "C") (pinfunction "COLLECTOR_C") (pintype "passive"))
      (node (ref "R32") (pin "1") (pinfunction "1_1") (pintype "passive"))
    )
    (net (code "27") (name "Net-(IC6A-X6)") (class "Default")
      (node (ref "IC6") (pin "2") (pinfunction "X6_2") (pintype "bidirectional"))
      (node (ref "OS16") (pin "C") (pinfunction "COLLECTOR_C") (pintype "passive"))
      (node (ref "R34") (pin "1") (pinfunction "1_1") (pintype "passive"))
    )
    (net (code "28") (name "Net-(IC6A-X7)") (class "Default")
      (node (ref "IC6") (pin "4") (pinfunction "X7_4") (pintype "bidirectional"))
      (node (ref "OS17") (pin "C") (pinfunction "COLLECTOR_C") (pintype "passive"))
      (node (ref "R36") (pin "1") (pinfunction "1_1") (pintype "passive"))
    )
    (net (code "29") (name "Net-(IC7A-X0)") (class "Default")
      (node (ref "IC7") (pin "13") (pinfunction "X0_13") (pintype "bidirectional"))
      (node (ref "OS18") (pin "C") (pinfunction "COLLECTOR_C") (pintype "passive"))
      (node (ref "R39") (pin "1") (pinfunction "1_1") (pintype "passive"))
    )
    (net (code "30") (name "Net-(IC7A-X1)") (class "Default")
      (node (ref "IC7") (pin "14") (pinfunction "X1_14") (pintype "bidirectional"))
      (node (ref "OS19") (pin "C") (pinfunction "COLLECTOR_C") (pintype "passive"))
      (node (ref "R41") (pin "1") (pinfunction "1_1") (pintype "passive"))
    )
    (net (code "31") (name "Net-(IC7A-X2)") (class "Default")
      (node (ref "IC7") (pin "15") (pinfunction "X2_15") (pintype "bidirectional"))
      (node (ref "OS20") (pin "C") (pinfunction "COLLECTOR_C") (pintype "passive"))
      (node (ref "R43") (pin "1") (pinfunction "1_1") (pintype "passive"))
    )
    (net (code "32") (name "Net-(IC7A-X3)") (class "Default")
      (node (ref "IC7") (pin "12") (pinfunction "X3_12") (pintype "bidirectional"))
      (node (ref "OS21") (pin "C") (pinfunction "COLLECTOR_C") (pintype "passive"))
      (node (ref "R45") (pin "1") (pinfunction "1_1") (pintype "passive"))
    )
    (net (code "33") (name "Net-(IC7A-X4)") (class "Default")
      (node (ref "IC7") (pin "1") (pinfunction "X4_1") (pintype "bidirectional"))
      (node (ref "OS22") (pin "C") (pinfunction "COLLECTOR_C") (pintype "passive"))
      (node (ref "R47") (pin "1") (pinfunction "1_1") (pintype "passive"))
    )
    (net (code "34") (name "Net-(IC7A-X5)") (class "Default")
      (node (ref "IC7") (pin "5") (pinfunction "X5_5") (pintype "bidirectional"))
      (node (ref "OS23") (pin "C") (pinfunction "COLLECTOR_C") (pintype "passive"))
      (node (ref "R49") (pin "1") (pinfunction "1_1") (pintype "passive"))
    )
    (net (code "35") (name "Net-(IC7A-X6)") (class "Default")
      (node (ref "IC7") (pin "2") (pinfunction "X6_2") (pintype "bidirectional"))
      (node (ref "OS24") (pin "C") (pinfunction "COLLECTOR_C") (pintype "passive"))
      (node (ref "R51") (pin "1") (pinfunction "1_1") (pintype "passive"))
    )
    (net (code "36") (name "Net-(IC7A-X7)") (class "Default")
      (node (ref "IC7") (pin "4") (pinfunction "X7_4") (pintype "bidirectional"))
      (node (ref "OS25") (pin "C") (pinfunction "COLLECTOR_C") (pintype "passive"))
      (node (ref "R53") (pin "1") (pinfunction "1_1") (pintype "passive"))
    )
    (net (code "37") (name "Net-(LED1-DO)") (class "Default")
      (node (ref "LED1") (pin "D_OUT") (pinfunction "DO_D_OUT") (pintype "output"))
      (node (ref "LED2") (pin "D_IN") (pinfunction "DI_D_IN") (pintype "input"))
    )
    (net (code "38") (name "Net-(LED2-DO)") (class "Default")
      (node (ref "LED2") (pin "D_OUT") (pinfunction "DO_D_OUT") (pintype "output"))
      (node (ref "LED3") (pin "D_IN") (pinfunction "DI_D_IN") (pintype "input"))
    )
    (net (code "39") (name "Net-(LED3-DO)") (class "Default")
      (node (ref "LED3") (pin "D_OUT") (pinfunction "DO_D_OUT") (pintype "output"))
      (node (ref "LED4") (pin "D_IN") (pinfunction "DI_D_IN") (pintype "input"))
    )
    (net (code "40") (name "Net-(LED4-DO)") (class "Default")
      (node (ref "LED4") (pin "D_OUT") (pinfunction "DO_D_OUT") (pintype "output"))
      (node (ref "LED5") (pin "D_IN") (pinfunction "DI_D_IN") (pintype "input"))
    )
    (net (code "41") (name "Net-(LED6-DO)") (class "Default")
      (node (ref "LED6") (pin "D_OUT") (pinfunction "DO_D_OUT") (pintype "output"))
      (node (ref "LED7") (pin "D_IN") (pinfunction "DI_D_IN") (pintype "input"))
    )
    (net (code "42") (name "Net-(LED7-DO)") (class "Default")
      (node (ref "LED7") (pin "D_OUT") (pinfunction "DO_D_OUT") (pintype "output"))
      (node (ref "LED8") (pin "D_IN") (pinfunction "DI_D_IN") (pintype "input"))
    )
    (net (code "43") (name "Net-(LED8-DO)") (class "Default")
      (node (ref "LED8") (pin "D_OUT") (pinfunction "DO_D_OUT") (pintype "output"))
      (node (ref "LED9") (pin "D_IN") (pinfunction "DI_D_IN") (pintype "input"))
    )
    (net (code "44") (name "Net-(LED10-DI)") (class "Default")
      (node (ref "LED10") (pin "D_IN") (pinfunction "DI_D_IN") (pintype "input"))
      (node (ref "LED9") (pin "D_OUT") (pinfunction "DO_D_OUT") (pintype "output"))
    )
    (net (code "45") (name "Net-(LED11-DO)") (class "Default")
      (node (ref "LED11") (pin "D_OUT") (pinfunction "DO_D_OUT") (pintype "output"))
      (node (ref "LED12") (pin "D_IN") (pinfunction "DI_D_IN") (pintype "input"))
    )
    (net (code "46") (name "Net-(LED12-DO)") (class "Default")
      (node (ref "LED12") (pin "D_OUT") (pinfunction "DO_D_OUT") (pintype "output"))
      (node (ref "LED13") (pin "D_IN") (pinfunction "DI_D_IN") (pintype "input"))
    )
    (net (code "47") (name "Net-(LED13-DO)") (class "Default")
      (node (ref "LED13") (pin "D_OUT") (pinfunction "DO_D_OUT") (pintype "output"))
      (node (ref "LED14") (pin "D_IN") (pinfunction "DI_D_IN") (pintype "input"))
    )
    (net (code "48") (name "Net-(LED14-DO)") (class "Default")
      (node (ref "LED14") (pin "D_OUT") (pinfunction "DO_D_OUT") (pintype "output"))
      (node (ref "LED15") (pin "D_IN") (pinfunction "DI_D_IN") (pintype "input"))
    )
    (net (code "49") (name "Net-(LED16-DO)") (class "Default")
      (node (ref "LED16") (pin "D_OUT") (pinfunction "DO_D_OUT") (pintype "output"))
      (node (ref "LED17") (pin "D_IN") (pinfunction "DI_D_IN") (pintype "input"))
    )
    (net (code "50") (name "Net-(LED17-DO)") (class "Default")
      (node (ref "LED17") (pin "D_OUT") (pinfunction "DO_D_OUT") (pintype "output"))
      (node (ref "LED18") (pin "D_IN") (pinfunction "DI_D_IN") (pintype "input"))
    )
    (net (code "51") (name "Net-(LED18-DO)") (class "Default")
      (node (ref "LED18") (pin "D_OUT") (pinfunction "DO_D_OUT") (pintype "output"))
      (node (ref "LED19") (pin "D_IN") (pinfunction "DI_D_IN") (pintype "input"))
    )
    (net (code "52") (name "Net-(LED19-DO)") (class "Default")
      (node (ref "LED19") (pin "D_OUT") (pinfunction "DO_D_OUT") (pintype "output"))
      (node (ref "LED20") (pin "D_IN") (pinfunction "DI_D_IN") (pintype "input"))
    )
    (net (code "53") (name "Net-(LED21-DO)") (class "Default")
      (node (ref "LED21") (pin "D_OUT") (pinfunction "DO_D_OUT") (pintype "output"))
      (node (ref "LED22") (pin "D_IN") (pinfunction "DI_D_IN") (pintype "input"))
    )
    (net (code "54") (name "Net-(LED22-DO)") (class "Default")
      (node (ref "LED22") (pin "D_OUT") (pinfunction "DO_D_OUT") (pintype "output"))
      (node (ref "LED23") (pin "D_IN") (pinfunction "DI_D_IN") (pintype "input"))
    )
    (net (code "55") (name "Net-(LED23-DO)") (class "Default")
      (node (ref "LED23") (pin "D_OUT") (pinfunction "DO_D_OUT") (pintype "output"))
      (node (ref "LED24") (pin "D_IN") (pinfunction "DI_D_IN") (pintype "input"))
    )
    (net (code "56") (name "Net-(LED24-DO)") (class "Default")
      (node (ref "LED24") (pin "D_OUT") (pinfunction "DO_D_OUT") (pintype "output"))
      (node (ref "LED25") (pin "D_IN") (pinfunction "DI_D_IN") (pintype "input"))
    )
    (net (code "57") (name "Net-(OS2-ANODE)") (class "Default")
      (node (ref "OS2") (pin "A") (pinfunction "ANODE_A") (pintype "passive"))
      (node (ref "R8") (pin "1") (pinfunction "1_1") (pintype "passive"))
    )
    (net (code "58") (name "Net-(OS3-ANODE)") (class "Default")
      (node (ref "OS3") (pin "A") (pinfunction "ANODE_A") (pintype "passive"))
      (node (ref "R10") (pin "1") (pinfunction "1_1") (pintype "passive"))
    )
    (net (code "59") (name "Net-(OS4-ANODE)") (class "Default")
      (node (ref "OS4") (pin "A") (pinfunction "ANODE_A") (pintype "passive"))
      (node (ref "R6") (pin "1") (pinfunction "1_1") (pintype "passive"))
    )
    (net (code "60") (name "Net-(OS5-ANODE)") (class "Default")
      (node (ref "OS5") (pin "A") (pinfunction "ANODE_A") (pintype "passive"))
      (node (ref "R12") (pin "1") (pinfunction "1_1") (pintype "passive"))
    )
    (net (code "61") (name "Net-(OS6-ANODE)") (class "Default")
      (node (ref "OS6") (pin "A") (pinfunction "ANODE_A") (pintype "passive"))
      (node (ref "R14") (pin "1") (pinfunction "1_1") (pintype "passive"))
    )
    (net (code "62") (name "Net-(OS7-ANODE)") (class "Default")
      (node (ref "OS7") (pin "A") (pinfunction "ANODE_A") (pintype "passive"))
      (node (ref "R16") (pin "1") (pinfunction "1_1") (pintype "passive"))
    )
    (net (code "63") (name "Net-(OS8-ANODE)") (class "Default")
      (node (ref "OS8") (pin "A") (pinfunction "ANODE_A") (pintype "passive"))
      (node (ref "R18") (pin "1") (pinfunction "1_1") (pintype "passive"))
    )
    (net (code "64") (name "Net-(OS9-ANODE)") (class "Default")
      (node (ref "OS9") (pin "A") (pinfunction "ANODE_A") (pintype "passive"))
      (node (ref "R20") (pin "1") (pinfunction "1_1") (pintype "passive"))
    )
    (net (code "65") (name "Net-(OS10-ANODE)") (class "Default")
      (node (ref "OS10") (pin "A") (pinfunction "ANODE_A") (pintype "passive"))
      (node (ref "R23") (pin "1") (pinfunction "1_1") (pintype "passive"))
    )
    (net (code "66") (name "Net-(OS11-ANODE)") (class "Default")
      (node (ref "OS11") (pin "A") (pinfunction "ANODE_A") (pintype "passive"))
      (node (ref "R25") (pin "1") (pinfunction "1_1") (pintype "passive"))
    )
    (net (code "67") (name "Net-(OS12-ANODE)") (class "Default")
      (node (ref "OS12") (pin "A") (pinfunction "ANODE_A") (pintype "passive"))
      (node (ref "R27") (pin "1") (pinfunction "1_1") (pintype "passive"))
    )
    (net (code "68") (name "Net-(OS13-ANODE)") (class "Default")
      (node (ref "OS13") (pin "A") (pinfunction "ANODE_A") (pintype "passive"))
      (node (ref "R29") (pin "1") (pinfunction "1_1") (pintype "passive"))
    )
    (net (code "69") (name "Net-(OS14-ANODE)") (class "Default")
      (node (ref "OS14") (pin "A") (pinfunction "ANODE_A") (pintype "passive"))
      (node (ref "R31") (pin "1") (pinfunction "1_1") (pintype "passive"))
    )
    (net (code "70") (name "Net-(OS15-ANODE)") (class "Default")
      (node (ref "OS15") (pin "A") (pinfunction "ANODE_A") (pintype "passive"))
      (node (ref "R33") (pin "1") (pinfunction "1_1") (pintype "passive"))
    )
    (net (code "71") (name "Net-(OS16-ANODE)") (class "Default")
      (node (ref "OS16") (pin "A") (pinfunction "ANODE_A") (pintype "passive"))
      (node (ref "R35") (pin "1") (pinfunction "1_1") (pintype "passive"))
    )
    (net (code "72") (name "Net-(OS17-ANODE)") (class "Default")
      (node (ref "OS17") (pin "A") (pinfunction "ANODE_A") (pintype "passive"))
      (node (ref "R37") (pin "1") (pinfunction "1_1") (pintype "passive"))
    )
    (net (code "73") (name "Net-(OS18-ANODE)") (class "Default")
      (node (ref "OS18") (pin "A") (pinfunction "ANODE_A") (pintype "passive"))
      (node (ref "R40") (pin "1") (pinfunction "1_1") (pintype "passive"))
    )
    (net (code "74") (name "Net-(OS19-ANODE)") (class "Default")
      (node (ref "OS19") (pin "A") (pinfunction "ANODE_A") (pintype "passive"))
      (node (ref "R42") (pin "1") (pinfunction "1_1") (pintype "passive"))
    )
    (net (code "75") (name "Net-(OS20-ANODE)") (class "Default")
      (node (ref "OS20") (pin "A") (pinfunction "ANODE_A") (pintype "passive"))
      (node (ref "R44") (pin "1") (pinfunction "1_1") (pintype "passive"))
    )
    (net (code "76") (name "Net-(OS21-ANODE)") (class "Default")
      (node (ref "OS21") (pin "A") (pinfunction "ANODE_A") (pintype "passive"))
      (node (ref "R46") (pin "1") (pinfunction "1_1") (pintype "passive"))
    )
    (net (code "77") (name "Net-(OS22-ANODE)") (class "Default")
      (node (ref "OS22") (pin "A") (pinfunction "ANODE_A") (pintype "passive"))
      (node (ref "R48") (pin "1") (pinfunction "1_1") (pintype "passive"))
    )
    (net (code "78") (name "Net-(OS23-ANODE)") (class "Default")
      (node (ref "OS23") (pin "A") (pinfunction "ANODE_A") (pintype "passive"))
      (node (ref "R50") (pin "1") (pinfunction "1_1") (pintype "passive"))
    )
    (net (code "79") (name "Net-(OS24-ANODE)") (class "Default")
      (node (ref "OS24") (pin "A") (pinfunction "ANODE_A") (pintype "passive"))
      (node (ref "R52") (pin "1") (pinfunction "1_1") (pintype "passive"))
    )
    (net (code "80") (name "Net-(OS25-ANODE)") (class "Default")
      (node (ref "OS25") (pin "A") (pinfunction "ANODE_A") (pintype "passive"))
      (node (ref "R54") (pin "1") (pinfunction "1_1") (pintype "passive"))
    )
    (net (code "81") (name "Net-(OS26-ANODE)") (class "Default")
      (node (ref "OS26") (pin "A") (pinfunction "ANODE_A") (pintype "passive"))
      (node (ref "R57") (pin "1") (pinfunction "1_1") (pintype "passive"))
    )
    (net (code "82") (name "Net-(Q2-S)") (class "Default")
      (node (ref "Q2") (pin "3") (pinfunction "S_3") (pintype "passive"))
      (node (ref "R10") (pin "2") (pinfunction "2_2") (pintype "passive"))
      (node (ref "R11") (pin "2") (pinfunction "2_2") (pintype "passive"))
      (node (ref "R12") (pin "2") (pinfunction "2_2") (pintype "passive"))
      (node (ref "R13") (pin "2") (pinfunction "2_2") (pintype "passive"))
      (node (ref "R14") (pin "2") (pinfunction "2_2") (pintype "passive"))
      (node (ref "R15") (pin "2") (pinfunction "2_2") (pintype "passive"))
      (node (ref "R16") (pin "2") (pinfunction "2_2") (pintype "passive"))
      (node (ref "R17") (pin "2") (pinfunction "2_2") (pintype "passive"))
      (node (ref "R18") (pin "2") (pinfunction "2_2") (pintype "passive"))
      (node (ref "R19") (pin "2") (pinfunction "2_2") (pintype "passive"))
      (node (ref "R20") (pin "2") (pinfunction "2_2") (pintype "passive"))
      (node (ref "R5") (pin "2") (pinfunction "2_2") (pintype "passive"))
      (node (ref "R6") (pin "2") (pinfunction "2_2") (pintype "passive"))
      (node (ref "R7") (pin "2") (pinfunction "2_2") (pintype "passive"))
      (node (ref "R8") (pin "2") (pinfunction "2_2") (pintype "passive"))
      (node (ref "R9") (pin "2") (pinfunction "2_2") (pintype "passive"))
    )
    (net (code "83") (name "Net-(Q3-S)") (class "Default")
      (node (ref "Q3") (pin "3") (pinfunction "S_3") (pintype "passive"))
      (node (ref "R22") (pin "2") (pinfunction "2_2") (pintype "passive"))
      (node (ref "R23") (pin "2") (pinfunction "2_2") (pintype "passive"))
      (node (ref "R24") (pin "2") (pinfunction "2_2") (pintype "passive"))
      (node (ref "R25") (pin "2") (pinfunction "2_2") (pintype "passive"))
      (node (ref "R26") (pin "2") (pinfunction "2_2") (pintype "passive"))
      (node (ref "R27") (pin "2") (pinfunction "2_2") (pintype "passive"))
      (node (ref "R28") (pin "2") (pinfunction "2_2") (pintype "passive"))
      (node (ref "R29") (pin "2") (pinfunction "2_2") (pintype "passive"))
      (node (ref "R30") (pin "2") (pinfunction "2_2") (pintype "passive"))
      (node (ref "R31") (pin "2") (pinfunction "2_2") (pintype "passive"))
      (node (ref "R32") (pin "2") (pinfunction "2_2") (pintype "passive"))
      (node (ref "R33") (pin "2") (pinfunction "2_2") (pintype "passive"))
      (node (ref "R34") (pin "2") (pinfunction "2_2") (pintype "passive"))
      (node (ref "R35") (pin "2") (pinfunction "2_2") (pintype "passive"))
      (node (ref "R36") (pin "2") (pinfunction "2_2") (pintype "passive"))
      (node (ref "R37") (pin "2") (pinfunction "2_2") (pintype "passive"))
    )
    (net (code "84") (name "Net-(Q4-S)") (class "Default")
      (node (ref "Q4") (pin "3") (pinfunction "S_3") (pintype "passive"))
      (node (ref "R39") (pin "2") (pinfunction "2_2") (pintype "passive"))
      (node (ref "R40") (pin "2") (pinfunction "2_2") (pintype "passive"))
      (node (ref "R41") (pin "2") (pinfunction "2_2") (pintype "passive"))
      (node (ref "R42") (pin "2") (pinfunction "2_2") (pintype "passive"))
      (node (ref "R43") (pin "2") (pinfunction "2_2") (pintype "passive"))
      (node (ref "R44") (pin "2") (pinfunction "2_2") (pintype "passive"))
      (node (ref "R45") (pin "2") (pinfunction "2_2") (pintype "passive"))
      (node (ref "R46") (pin "2") (pinfunction "2_2") (pintype "passive"))
      (node (ref "R47") (pin "2") (pinfunction "2_2") (pintype "passive"))
      (node (ref "R48") (pin "2") (pinfunction "2_2") (pintype "passive"))
      (node (ref "R49") (pin "2") (pinfunction "2_2") (pintype "passive"))
      (node (ref "R50") (pin "2") (pinfunction "2_2") (pintype "passive"))
      (node (ref "R51") (pin "2") (pinfunction "2_2") (pintype "passive"))
      (node (ref "R52") (pin "2") (pinfunction "2_2") (pintype "passive"))
      (node (ref "R53") (pin "2") (pinfunction "2_2") (pintype "passive"))
      (node (ref "R54") (pin "2") (pinfunction "2_2") (pintype "passive"))
      (node (ref "R56") (pin "2") (pinfunction "2_2") (pintype "passive"))
      (node (ref "R57") (pin "2") (pinfunction "2_2") (pintype "passive"))
    )
    (net (code "85") (name "SECTION_1_EN") (class "Default")
      (node (ref "IC4") (pin "1") (pinfunction "Y0_1") (pintype "bidirectional"))
      (node (ref "Q2") (pin "1") (pinfunction "G_1") (pintype "passive"))
      (node (ref "R21") (pin "1") (pinfunction "1_1") (pintype "passive"))
    )
    (net (code "86") (name "SECTION_2_EN") (class "Default")
      (node (ref "IC4") (pin "5") (pinfunction "Y1_5") (pintype "bidirectional"))
      (node (ref "Q3") (pin "1") (pinfunction "G_1") (pintype "passive"))
      (node (ref "R38") (pin "1") (pinfunction "1_1") (pintype "passive"))
    )
    (net (code "87") (name "SECTION_3_EN") (class "Default")
      (node (ref "IC4") (pin "2") (pinfunction "Y2_2") (pintype "bidirectional"))
      (node (ref "IC4") (pin "4") (pinfunction "Y3_4") (pintype "bidirectional"))
      (node (ref "Q4") (pin "1") (pinfunction "G_1") (pintype "passive"))
      (node (ref "R55") (pin "1") (pinfunction "1_1") (pintype "passive"))
    )
    (net (code "88") (name "SENSOR") (class "Default")
      (node (ref "IC4") (pin "13") (pinfunction "X_13") (pintype "bidirectional"))
      (node (ref "J1") (pin "6") (pinfunction "6_6") (pintype "passive"))
    )
    (net (code "89") (name "unconnected-(LED1-DI-PadD_IN)") (class "Default")
      (node (ref "LED1") (pin "D_IN") (pinfunction "DI_D_IN") (pintype "input"))
    )
    (net (code "90") (name "unconnected-(LED5-DO-PadD_OUT)") (class "Default")
      (node (ref "LED5") (pin "D_OUT") (pinfunction "DO_D_OUT") (pintype "output"))
    )
    (net (code "91") (name "unconnected-(LED6-DI-PadD_IN)") (class "Default")
      (node (ref "LED6") (pin "D_IN") (pinfunction "DI_D_IN") (pintype "input"))
    )
    (net (code "92") (name "unconnected-(LED10-DO-PadD_OUT)") (class "Default")
      (node (ref "LED10") (pin "D_OUT") (pinfunction "DO_D_OUT") (pintype "output"))
    )
    (net (code "93") (name "unconnected-(LED11-DI-PadD_IN)") (class "Default")
      (node (ref "LED11") (pin "D_IN") (pinfunction "DI_D_IN") (pintype "input"))
    )
    (net (code "94") (name "unconnected-(LED15-DO-PadD_OUT)") (class "Default")
      (node (ref "LED15") (pin "D_OUT") (pinfunction "DO_D_OUT") (pintype "output"))
    )
    (net (code "95") (name "unconnected-(LED16-DI-PadD_IN)") (class "Default")
      (node (ref "LED16") (pin "D_IN") (pinfunction "DI_D_IN") (pintype "input"))
    )
    (net (code "96") (name "unconnected-(LED20-DO-PadD_OUT)") (class "Default")
      (node (ref "LED20") (pin "D_OUT") (pinfunction "DO_D_OUT") (pintype "output"))
    )
    (net (code "97") (name "unconnected-(LED21-DI-PadD_IN)") (class "Default")
      (node (ref "LED21") (pin "D_IN") (pinfunction "DI_D_IN") (pintype "input"))
    )
    (net (code "98") (name "unconnected-(LED25-DO-PadD_OUT)") (class "Default")
      (node (ref "LED25") (pin "D_OUT") (pinfunction "DO_D_OUT") (pintype "output"))
    )
  )
)
